# PCB_CHECK_MAIN233-201219.net
KiCad netlist of a schematic drawn in Altium Designer
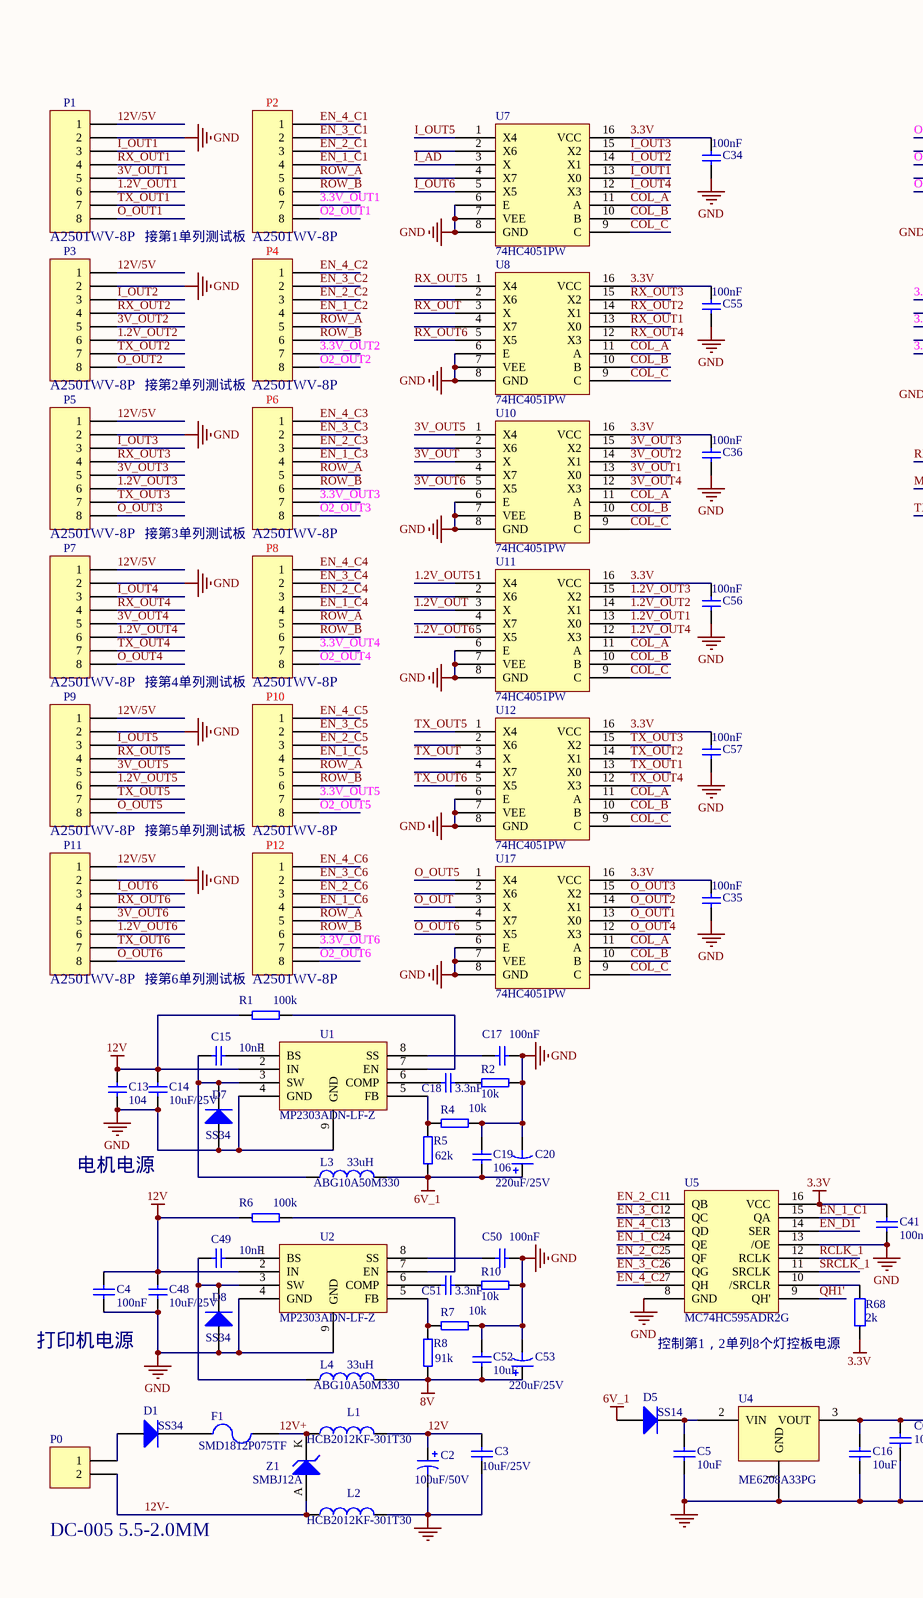
[diagram p0: PCB_CHECK_MAIN233-201219.SchDoc, left]
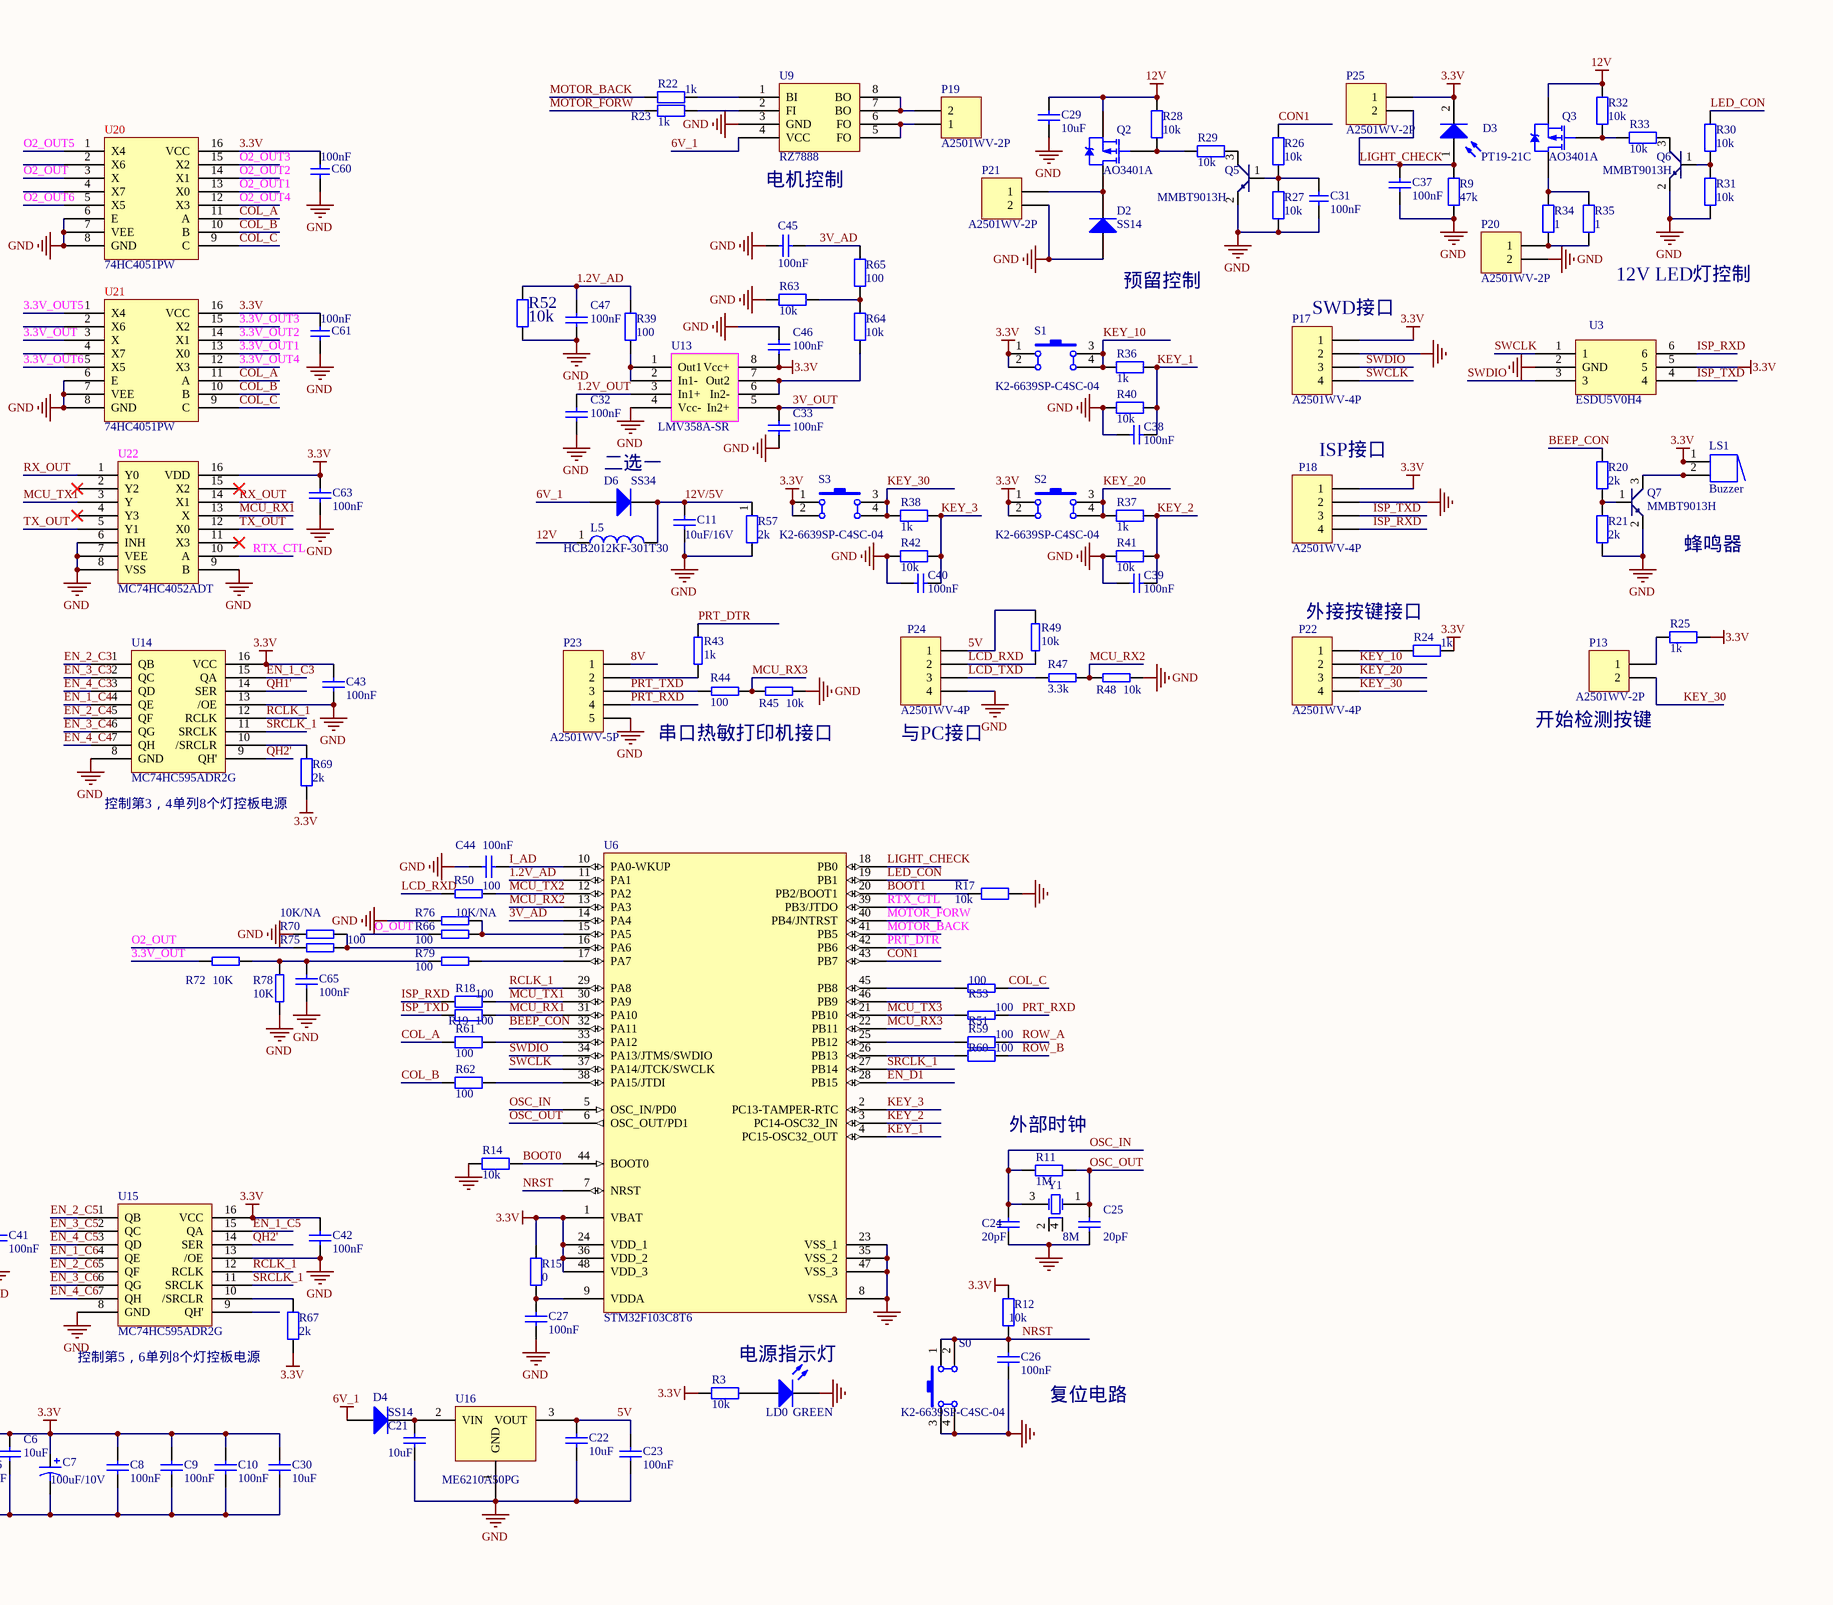
[diagram p1: PCB_CHECK_MAIN233-201219.SchDoc, right]

(export (version "E")
  (design (tool "Eeschema 10.0.6"))
  (components
    (comp (ref "C2")
      (value "100uF/50V")
      (footprint "RB-6*9")
      (description "Polarized Capacitor (Radial)")
      (fields (field (name "PUBLISHER") "Altium Limited"))
      (libsource (lib "Miscellaneous Devices") (part "Cap Pol1"))
    )
    (comp (ref "C3")
      (value "10uF/25V")
      (footprint "C0805")
      (description "Capacitor")
      (fields (field (name "PUBLISHER") "Altium Limited"))
      (libsource (lib "Miscellaneous Devices") (part "Cap"))
    )
    (comp (ref "C4")
      (value "100nF")
      (footprint "C0603")
      (description "Capacitor")
      (fields (field (name "PUBLISHER") "Altium Limited"))
      (libsource (lib "Miscellaneous Devices") (part "Cap"))
    )
    (comp (ref "C5")
      (value "10uF")
      (footprint "C0603")
      (description "Capacitor")
      (fields (field (name "PUBLISHER") "Altium Limited"))
      (libsource (lib "Miscellaneous Devices") (part "Cap"))
    )
    (comp (ref "C6")
      (value "10uF")
      (footprint "C0603")
      (description "Capacitor")
      (fields (field (name "PUBLISHER") "Altium Limited"))
      (libsource (lib "Miscellaneous Devices") (part "Cap"))
    )
    (comp (ref "C7")
      (value "100uF/10V")
      (footprint "C3528")
      (description "Polarized Capacitor (Radial)")
      (fields (field (name "PUBLISHER") "Altium Limited"))
      (libsource (lib "Miscellaneous Devices") (part "Cap Pol1"))
    )
    (comp (ref "C8")
      (value "100nF")
      (footprint "C0603")
      (description "Capacitor")
      (fields (field (name "PUBLISHER") "Altium Limited"))
      (libsource (lib "Miscellaneous Devices") (part "Cap"))
    )
    (comp (ref "C9")
      (value "100nF")
      (footprint "C0603")
      (description "Capacitor")
      (fields (field (name "PUBLISHER") "Altium Limited"))
      (libsource (lib "Miscellaneous Devices") (part "Cap"))
    )
    (comp (ref "C10")
      (value "100nF")
      (footprint "C0603")
      (description "Capacitor")
      (fields (field (name "PUBLISHER") "Altium Limited"))
      (libsource (lib "Miscellaneous Devices") (part "Cap"))
    )
    (comp (ref "C11")
      (value "10uF/16V")
      (footprint "C0603")
      (description "Capacitor")
      (fields (field (name "PUBLISHER") "Altium Limited"))
      (libsource (lib "Miscellaneous Devices") (part "Cap"))
    )
    (comp (ref "C13")
      (value "104")
      (footprint "C0603")
      (description "电容器")
      (libsource (lib "*") (part "Capacitor"))
    )
    (comp (ref "C14")
      (value "10uF/25V")
      (footprint "My Footprint View:C0805")
      (description "电容器")
      (libsource (lib "*") (part "Capacitor"))
    )
    (comp (ref "C15")
      (value "10nF")
      (footprint "C0603")
      (description "电容器")
      (libsource (lib "*") (part "Capacitor"))
    )
    (comp (ref "C16")
      (value "10uF")
      (footprint "C0603")
      (description "Capacitor")
      (fields (field (name "PUBLISHER") "Altium Limited"))
      (libsource (lib "Miscellaneous Devices") (part "Cap"))
    )
    (comp (ref "C17")
      (value "100nF")
      (footprint "C0603")
      (description "电容器")
      (libsource (lib "*") (part "Capacitor"))
    )
    (comp (ref "C18")
      (value "3.3nF")
      (footprint "C0603")
      (description "电容器")
      (libsource (lib "*") (part "Capacitor"))
    )
    (comp (ref "C19")
      (value "106")
      (footprint "C0603")
      (description "电容器")
      (libsource (lib "*") (part "Capacitor"))
    )
    (comp (ref "C20")
      (value "220uF/25V")
      (footprint "RB-6*9")
      (description "Polarized Capacitor (Radial)")
      (fields (field (name "PUBLISHER") "Altium Limited"))
      (libsource (lib "Miscellaneous Devices") (part "Cap Pol1"))
    )
    (comp (ref "C21")
      (value "10uF")
      (footprint "C0603")
      (description "Capacitor")
      (fields (field (name "PUBLISHER") "Altium Limited"))
      (libsource (lib "Miscellaneous Devices") (part "Cap"))
    )
    (comp (ref "C22")
      (value "10uF")
      (footprint "C0603")
      (description "Capacitor")
      (fields (field (name "PUBLISHER") "Altium Limited"))
      (libsource (lib "Miscellaneous Devices") (part "Cap"))
    )
    (comp (ref "C23")
      (value "100nF")
      (footprint "C0603")
      (description "Capacitor")
      (fields (field (name "PUBLISHER") "Altium Limited"))
      (libsource (lib "Miscellaneous Devices") (part "Cap"))
    )
    (comp (ref "C24")
      (value "20pF")
      (footprint "C0603")
      (description "Capacitor")
      (fields (field (name "PUBLISHER") "Altium Limited"))
      (libsource (lib "Miscellaneous Devices") (part "Cap"))
    )
    (comp (ref "C25")
      (value "20pF")
      (footprint "C0603")
      (description "Capacitor")
      (fields (field (name "PUBLISHER") "Altium Limited"))
      (libsource (lib "Miscellaneous Devices") (part "Cap"))
    )
    (comp (ref "C26")
      (value "100nF")
      (footprint "C0603")
      (description "Capacitor")
      (fields (field (name "PUBLISHER") "Altium Limited"))
      (libsource (lib "Miscellaneous Devices") (part "Cap"))
    )
    (comp (ref "C27")
      (value "100nF")
      (footprint "C0603")
      (description "Capacitor")
      (fields (field (name "PUBLISHER") "Altium Limited"))
      (libsource (lib "Miscellaneous Devices") (part "Cap"))
    )
    (comp (ref "C29")
      (value "10uF")
      (footprint "C0603")
      (description "Capacitor")
      (fields (field (name "PUBLISHER") "Altium Limited"))
      (libsource (lib "Miscellaneous Devices") (part "Cap"))
    )
    (comp (ref "C30")
      (value "10uF")
      (footprint "C0603")
      (description "Capacitor")
      (fields (field (name "PUBLISHER") "Altium Limited"))
      (libsource (lib "Miscellaneous Devices") (part "Cap"))
    )
    (comp (ref "C31")
      (value "100nF")
      (footprint "C0603")
      (description "电容器")
      (libsource (lib "*") (part "Capacitor"))
    )
    (comp (ref "C32")
      (value "100nF")
      (footprint "C0603")
      (description "Capacitor")
      (fields (field (name "PUBLISHER") "Altium Limited"))
      (libsource (lib "Miscellaneous Devices") (part "Cap"))
    )
    (comp (ref "C33")
      (value "100nF")
      (footprint "C0603")
      (description "Capacitor")
      (fields (field (name "PUBLISHER") "Altium Limited"))
      (libsource (lib "Miscellaneous Devices") (part "Cap"))
    )
    (comp (ref "C34")
      (value "100nF")
      (footprint "C0603")
      (description "电容器")
      (libsource (lib "*") (part "Capacitor"))
    )
    (comp (ref "C35")
      (value "100nF")
      (footprint "C0603")
      (description "电容器")
      (libsource (lib "*") (part "Capacitor"))
    )
    (comp (ref "C36")
      (value "100nF")
      (footprint "C0603")
      (description "电容器")
      (libsource (lib "*") (part "Capacitor"))
    )
    (comp (ref "C37")
      (value "100nF")
      (footprint "C0603")
      (description "Capacitor")
      (fields (field (name "PUBLISHER") "Altium Limited"))
      (libsource (lib "Miscellaneous Devices") (part "Cap"))
    )
    (comp (ref "C38")
      (value "100nF")
      (footprint "C0603")
      (description "电容器")
      (libsource (lib "*") (part "Capacitor"))
    )
    (comp (ref "C39")
      (value "100nF")
      (footprint "C0603")
      (description "电容器")
      (libsource (lib "*") (part "Capacitor"))
    )
    (comp (ref "C40")
      (value "100nF")
      (footprint "C0603")
      (description "电容器")
      (libsource (lib "*") (part "Capacitor"))
    )
    (comp (ref "C41")
      (value "100nF")
      (footprint "C0603")
      (description "Capacitor")
      (fields (field (name "PUBLISHER") "Altium Limited"))
      (libsource (lib "Miscellaneous Devices") (part "Cap"))
    )
    (comp (ref "C42")
      (value "100nF")
      (footprint "C0603")
      (description "Capacitor")
      (fields (field (name "PUBLISHER") "Altium Limited"))
      (libsource (lib "Miscellaneous Devices") (part "Cap"))
    )
    (comp (ref "C43")
      (value "100nF")
      (footprint "C0603")
      (description "Capacitor")
      (fields (field (name "PUBLISHER") "Altium Limited"))
      (libsource (lib "Miscellaneous Devices") (part "Cap"))
    )
    (comp (ref "C44")
      (value "100nF")
      (footprint "C0603")
      (description "Capacitor")
      (fields (field (name "PUBLISHER") "Altium Limited"))
      (libsource (lib "Miscellaneous Devices") (part "Cap"))
    )
    (comp (ref "C45")
      (value "100nF")
      (footprint "C0603")
      (description "Capacitor")
      (fields (field (name "PUBLISHER") "Altium Limited"))
      (libsource (lib "Miscellaneous Devices") (part "Cap"))
    )
    (comp (ref "C46")
      (value "100nF")
      (footprint "C0603")
      (description "Capacitor")
      (fields (field (name "PUBLISHER") "Altium Limited"))
      (libsource (lib "Miscellaneous Devices") (part "Cap"))
    )
    (comp (ref "C47")
      (value "100nF")
      (footprint "C0603")
      (description "Capacitor")
      (fields (field (name "PUBLISHER") "Altium Limited"))
      (libsource (lib "Miscellaneous Devices") (part "Cap"))
    )
    (comp (ref "C48")
      (value "10uF/25V")
      (footprint "My Footprint View:C0805")
      (description "电容器")
      (libsource (lib "*") (part "Capacitor"))
    )
    (comp (ref "C49")
      (value "10nF")
      (footprint "C0603")
      (description "电容器")
      (libsource (lib "*") (part "Capacitor"))
    )
    (comp (ref "C50")
      (value "100nF")
      (footprint "C0603")
      (description "电容器")
      (libsource (lib "*") (part "Capacitor"))
    )
    (comp (ref "C51")
      (value "3.3nF")
      (footprint "C0603")
      (description "电容器")
      (libsource (lib "*") (part "Capacitor"))
    )
    (comp (ref "C52")
      (value "10uF")
      (footprint "C0603")
      (description "电容器")
      (libsource (lib "*") (part "Capacitor"))
    )
    (comp (ref "C53")
      (value "220uF/25V")
      (footprint "RB-6*9")
      (description "Polarized Capacitor (Radial)")
      (fields (field (name "PUBLISHER") "Altium Limited"))
      (libsource (lib "Miscellaneous Devices") (part "Cap Pol1"))
    )
    (comp (ref "C55")
      (value "100nF")
      (footprint "C0603")
      (description "电容器")
      (libsource (lib "*") (part "Capacitor"))
    )
    (comp (ref "C56")
      (value "100nF")
      (footprint "C0603")
      (description "电容器")
      (libsource (lib "*") (part "Capacitor"))
    )
    (comp (ref "C57")
      (value "100nF")
      (footprint "C0603")
      (description "电容器")
      (libsource (lib "*") (part "Capacitor"))
    )
    (comp (ref "C60")
      (value "100nF")
      (footprint "C0603")
      (description "电容器")
      (libsource (lib "*") (part "Capacitor"))
    )
    (comp (ref "C61")
      (value "100nF")
      (footprint "C0603")
      (description "电容器")
      (libsource (lib "*") (part "Capacitor"))
    )
    (comp (ref "C63")
      (value "100nF")
      (footprint "C0603")
      (description "Capacitor")
      (fields (field (name "PUBLISHER") "Altium Limited"))
      (libsource (lib "Miscellaneous Devices") (part "Cap"))
    )
    (comp (ref "C65")
      (value "100nF")
      (footprint "C0603")
      (description "Capacitor")
      (fields (field (name "PUBLISHER") "Altium Limited"))
      (libsource (lib "Miscellaneous Devices") (part "Cap"))
    )
    (comp (ref "D1")
      (value "SS34")
      (footprint "SMB")
      (description "1 Amp General Purpose Rectifier")
      (fields (field (name "PUBLISHER") "Altium Limited"))
      (libsource (lib "Miscellaneous Devices") (part "Diode 1N4001"))
    )
    (comp (ref "D2")
      (value "SS14")
      (footprint "SOD-123F")
      (description "通用二极管")
      (fields (field (name "PUBLISHER") "Altium Limited"))
      (libsource (lib "*") (part "Diode"))
    )
    (comp (ref "D3")
      (value "PT19-21C")
      (footprint "LED-0603")
      (description "Photosensitive Diode")
      (fields (field (name "PUBLISHER") "Altium Limited"))
      (libsource (lib "Miscellaneous Devices") (part "Photo Sen"))
    )
    (comp (ref "D4")
      (value "SS14")
      (footprint "SOD-123F")
      (description "1 Amp General Purpose Rectifier")
      (fields (field (name "PUBLISHER") "Altium Limited"))
      (libsource (lib "Miscellaneous Devices") (part "Diode 1N4001"))
    )
    (comp (ref "D5")
      (value "SS14")
      (footprint "SOD-123F")
      (description "1 Amp General Purpose Rectifier")
      (fields (field (name "PUBLISHER") "Altium Limited"))
      (libsource (lib "Miscellaneous Devices") (part "Diode 1N4001"))
    )
    (comp (ref "D6")
      (value "SS34")
      (footprint "SMB")
      (description "1 Amp General Purpose Rectifier")
      (fields (field (name "PUBLISHER") "Altium Limited"))
      (libsource (lib "Miscellaneous Devices") (part "Diode 1N4001"))
    )
    (comp (ref "D7")
      (value "SS34")
      (footprint "PCBLIB:SMB")
      (description "通用二极管")
      (fields (field (name "PUBLISHER") "Altium Limited"))
      (libsource (lib "*") (part "Diode"))
    )
    (comp (ref "D8")
      (value "SS34")
      (footprint "PCBLIB:SMB")
      (description "通用二极管")
      (fields (field (name "PUBLISHER") "Altium Limited"))
      (libsource (lib "*") (part "Diode"))
    )
    (comp (ref "F1")
      (value "SMD1812P075TF")
      (footprint "1812")
      (description "Fuse")
      (fields (field (name "PUBLISHER") "Altium Limited"))
      (libsource (lib "Miscellaneous Devices") (part "Fuse 2"))
    )
    (comp (ref "L1")
      (value "HCB2012KF-301T30")
      (footprint "R0805")
      (description "Inductor")
      (fields (field (name "PUBLISHER") "Altium Limited"))
      (libsource (lib "Miscellaneous Devices") (part "Inductor"))
    )
    (comp (ref "L2")
      (value "HCB2012KF-301T30")
      (footprint "R0805")
      (description "Inductor")
      (fields (field (name "PUBLISHER") "Altium Limited"))
      (libsource (lib "Miscellaneous Devices") (part "Inductor"))
    )
    (comp (ref "L3")
      (value "33uH")
      (footprint "L1040")
      (description "Inductor")
      (fields (field (name "ALTIUM_VALUE") "ABG10A50M330") (field (name "PUBLISHER") "Altium Limited"))
      (libsource (lib "") (part "Inductor_2"))
    )
    (comp (ref "L4")
      (value "33uH")
      (footprint "L1040")
      (description "Inductor")
      (fields (field (name "ALTIUM_VALUE") "ABG10A50M330") (field (name "PUBLISHER") "Altium Limited"))
      (libsource (lib "") (part "Inductor_2"))
    )
    (comp (ref "L5")
      (value "HCB2012KF-301T30")
      (footprint "R0805")
      (description "Inductor")
      (fields (field (name "PUBLISHER") "Altium Limited"))
      (libsource (lib "") (part "Inductor_1"))
    )
    (comp (ref "LD0")
      (value "GREEN")
      (footprint "LED-0603")
      (description "LED灯")
      (fields (field (name "PUBLISHER") "Altium Limited"))
      (libsource (lib "*") (part "LED0"))
    )
    (comp (ref "LS1")
      (value "Buzzer")
      (footprint "BUZZER-small")
      (description "Magnetic Transducer Buzzer")
      (fields (field (name "PUBLISHER") "Altium Limited"))
      (libsource (lib "PCB_Project2") (part "Buzzer"))
    )
    (comp (ref "P0")
      (value "DC-005 5.5-2.0MM")
      (footprint "DC-005A")
      (description "Header, 2-Pin")
      (fields (field (name "PUBLISHER") "Altium Limited"))
      (libsource (lib "Miscellaneous Connectors") (part "Header 2"))
    )
    (comp (ref "P1")
      (value "A2501WV-8P")
      (footprint "XH2.5-8P")
      (description "Header, 8-Pin")
      (fields (field (name "PUBLISHER") "Altium Limited"))
      (libsource (lib "Miscellaneous Connectors") (part "Header 8"))
    )
    (comp (ref "P2")
      (value "A2501WV-8P")
      (footprint "XH2.5-8P")
      (description "Header, 8-Pin")
      (fields (field (name "PUBLISHER") "Altium Limited"))
      (libsource (lib "Miscellaneous Connectors") (part "Header 8"))
    )
    (comp (ref "P3")
      (value "A2501WV-8P")
      (footprint "XH2.5-8P")
      (description "Header, 8-Pin")
      (fields (field (name "PUBLISHER") "Altium Limited"))
      (libsource (lib "Miscellaneous Connectors") (part "Header 8"))
    )
    (comp (ref "P4")
      (value "A2501WV-8P")
      (footprint "XH2.5-8P")
      (description "Header, 8-Pin")
      (fields (field (name "PUBLISHER") "Altium Limited"))
      (libsource (lib "Miscellaneous Connectors") (part "Header 8"))
    )
    (comp (ref "P5")
      (value "A2501WV-8P")
      (footprint "XH2.5-8P")
      (description "Header, 8-Pin")
      (fields (field (name "PUBLISHER") "Altium Limited"))
      (libsource (lib "Miscellaneous Connectors") (part "Header 8"))
    )
    (comp (ref "P6")
      (value "A2501WV-8P")
      (footprint "XH2.5-8P")
      (description "Header, 8-Pin")
      (fields (field (name "PUBLISHER") "Altium Limited"))
      (libsource (lib "Miscellaneous Connectors") (part "Header 8"))
    )
    (comp (ref "P7")
      (value "A2501WV-8P")
      (footprint "XH2.5-8P")
      (description "Header, 8-Pin")
      (fields (field (name "PUBLISHER") "Altium Limited"))
      (libsource (lib "Miscellaneous Connectors") (part "Header 8"))
    )
    (comp (ref "P8")
      (value "A2501WV-8P")
      (footprint "XH2.5-8P")
      (description "Header, 8-Pin")
      (fields (field (name "PUBLISHER") "Altium Limited"))
      (libsource (lib "Miscellaneous Connectors") (part "Header 8"))
    )
    (comp (ref "P9")
      (value "A2501WV-8P")
      (footprint "XH2.5-8P")
      (description "Header, 8-Pin")
      (fields (field (name "PUBLISHER") "Altium Limited"))
      (libsource (lib "Miscellaneous Connectors") (part "Header 8"))
    )
    (comp (ref "P10")
      (value "A2501WV-8P")
      (footprint "XH2.5-8P")
      (description "Header, 8-Pin")
      (fields (field (name "PUBLISHER") "Altium Limited"))
      (libsource (lib "Miscellaneous Connectors") (part "Header 8"))
    )
    (comp (ref "P11")
      (value "A2501WV-8P")
      (footprint "XH2.5-8P")
      (description "Header, 8-Pin")
      (fields (field (name "PUBLISHER") "Altium Limited"))
      (libsource (lib "Miscellaneous Connectors") (part "Header 8"))
    )
    (comp (ref "P12")
      (value "A2501WV-8P")
      (footprint "XH2.5-8P")
      (description "Header, 8-Pin")
      (fields (field (name "PUBLISHER") "Altium Limited"))
      (libsource (lib "Miscellaneous Connectors") (part "Header 8"))
    )
    (comp (ref "P13")
      (value "A2501WV-2P")
      (footprint "XH2.5-2P")
      (description "Header, 2-Pin")
      (fields (field (name "PUBLISHER") "Altium Limited"))
      (libsource (lib "*") (part "Header 2"))
    )
    (comp (ref "P17")
      (value "A2501WV-4P")
      (footprint "XH2.5-4P")
      (description "Header, 4-Pin")
      (fields (field (name "PUBLISHER") "Altium Limited"))
      (libsource (lib "*") (part "Header 4"))
    )
    (comp (ref "P18")
      (value "A2501WV-4P")
      (footprint "XH2.5-4P")
      (description "Header, 4-Pin")
      (fields (field (name "PUBLISHER") "Altium Limited"))
      (libsource (lib "*") (part "Header 4"))
    )
    (comp (ref "P19")
      (value "A2501WV-2P")
      (footprint "XH2.5-2P")
      (description "Header, 2-Pin")
      (fields (field (name "PUBLISHER") "Altium Limited"))
      (libsource (lib "") (part "Header 2_1"))
    )
    (comp (ref "P20")
      (value "A2501WV-2P")
      (footprint "XH2.5-2P")
      (description "Header, 2-Pin")
      (fields (field (name "PUBLISHER") "Altium Limited"))
      (libsource (lib "*") (part "Header 2"))
    )
    (comp (ref "P21")
      (value "A2501WV-2P")
      (footprint "XH2.5-2P")
      (description "Header, 2-Pin")
      (fields (field (name "PUBLISHER") "Altium Limited"))
      (libsource (lib "*") (part "Header 2"))
    )
    (comp (ref "P22")
      (value "A2501WV-4P")
      (footprint "XH2.5-4P")
      (description "Header, 4-Pin")
      (fields (field (name "PUBLISHER") "Altium Limited"))
      (libsource (lib "*") (part "Header 4"))
    )
    (comp (ref "P23")
      (value "A2501WV-5P")
      (footprint "PcbLib1:XH2.5-5P")
      (description "Header, 5-Pin")
      (fields (field (name "PUBLISHER") "Altium Limited"))
      (libsource (lib "Miscellaneous Connectors") (part "Header 5"))
    )
    (comp (ref "P24")
      (value "A2501WV-4P")
      (footprint "XH2.5-4P")
      (description "Header, 4-Pin")
      (fields (field (name "PUBLISHER") "Altium Limited"))
      (libsource (lib "*") (part "Header 4"))
    )
    (comp (ref "P25")
      (value "A2501WV-2P")
      (footprint "XH2.5-2P")
      (description "Header, 2-Pin")
      (fields (field (name "PUBLISHER") "Altium Limited"))
      (libsource (lib "*") (part "Header 2"))
    )
    (comp (ref "Q2")
      (value "AO3401A")
      (footprint "SOT-23")
      (description "P-Channel MOSFET")
      (fields (field (name "PUBLISHER") "Altium Limited"))
      (libsource (lib "MY_STD_SCH") (part "MY_MOSFET-P"))
    )
    (comp (ref "Q3")
      (value "AO3401A")
      (footprint "SOT-23")
      (description "P-Channel MOSFET")
      (fields (field (name "PUBLISHER") "Altium Limited"))
      (libsource (lib "MY_STD_SCH") (part "MY_MOSFET-P"))
    )
    (comp (ref "Q5")
      (value "MMBT9013H")
      (footprint "SOT-23")
      (description "8050/BCW846/BCW847")
      (libsource (lib "MY_STD_SCH") (part "MY_NPN"))
    )
    (comp (ref "Q6")
      (value "MMBT9013H")
      (footprint "SOT-23")
      (description "8050/BCW846/BCW847")
      (libsource (lib "MY_STD_SCH") (part "MY_NPN"))
    )
    (comp (ref "Q7")
      (value "MMBT9013H")
      (footprint "SOT-23")
      (description "8050/BCW846/BCW847")
      (libsource (lib "MY_STD_SCH") (part "MY_NPN"))
    )
    (comp (ref "R1")
      (value "100k")
      (footprint "R0603")
      (description "电阻器")
      (libsource (lib "*") (part "Resistance"))
    )
    (comp (ref "R2")
      (value "10k")
      (footprint "R0603")
      (description "电阻器")
      (libsource (lib "*") (part "Resistance"))
    )
    (comp (ref "R3")
      (value "10k")
      (footprint "R0603")
      (description "Resistor")
      (fields (field (name "PUBLISHER") "Altium Limited"))
      (libsource (lib "") (part "Res2_1"))
    )
    (comp (ref "R4")
      (value "10k")
      (footprint "R0603")
      (description "电阻器")
      (libsource (lib "*") (part "Resistance"))
    )
    (comp (ref "R5")
      (value "62k")
      (footprint "R0603")
      (description "电阻器")
      (libsource (lib "*") (part "Resistance"))
    )
    (comp (ref "R6")
      (value "100k")
      (footprint "R0603")
      (description "电阻器")
      (libsource (lib "*") (part "Resistance"))
    )
    (comp (ref "R7")
      (value "10k")
      (footprint "R0603")
      (description "电阻器")
      (libsource (lib "*") (part "Resistance"))
    )
    (comp (ref "R8")
      (value "91k")
      (footprint "R0603")
      (description "电阻器")
      (libsource (lib "*") (part "Resistance"))
    )
    (comp (ref "R9")
      (value "47k")
      (footprint "R0603")
      (description "Resistor")
      (fields (field (name "PUBLISHER") "Altium Limited"))
      (libsource (lib "") (part "Res2_2"))
    )
    (comp (ref "R10")
      (value "10k")
      (footprint "R0603")
      (description "电阻器")
      (libsource (lib "*") (part "Resistance"))
    )
    (comp (ref "R11")
      (value "1M")
      (footprint "R0603")
      (description "Resistor")
      (fields (field (name "PUBLISHER") "Altium Limited"))
      (libsource (lib "") (part "Res2_1"))
    )
    (comp (ref "R12")
      (value "10k")
      (footprint "R0603")
      (description "Resistor")
      (fields (field (name "PUBLISHER") "Altium Limited"))
      (libsource (lib "") (part "Res2_4"))
    )
    (comp (ref "R14")
      (value "10k")
      (footprint "R0603")
      (description "Resistor")
      (fields (field (name "PUBLISHER") "Altium Limited"))
      (libsource (lib "") (part "Res2_1"))
    )
    (comp (ref "R15")
      (value "0")
      (footprint "R0603")
      (description "Resistor")
      (fields (field (name "PUBLISHER") "Altium Limited"))
      (libsource (lib "") (part "Res2_4"))
    )
    (comp (ref "R17")
      (value "10k")
      (footprint "R0603")
      (description "Resistor")
      (fields (field (name "PUBLISHER") "Altium Limited"))
      (libsource (lib "Miscellaneous Devices") (part "Res2"))
    )
    (comp (ref "R18")
      (value "100")
      (footprint "R0603")
      (description "Resistor")
      (fields (field (name "PUBLISHER") "Altium Limited"))
      (libsource (lib "") (part "Res2_1"))
    )
    (comp (ref "R19")
      (value "100")
      (footprint "R0603")
      (description "Resistor")
      (fields (field (name "PUBLISHER") "Altium Limited"))
      (libsource (lib "") (part "Res2_1"))
    )
    (comp (ref "R20")
      (value "2k")
      (footprint "R0603")
      (description "Resistor")
      (fields (field (name "PUBLISHER") "Altium Limited"))
      (libsource (lib "") (part "Res2_2"))
    )
    (comp (ref "R21")
      (value "2k")
      (footprint "R0603")
      (description "Resistor")
      (fields (field (name "PUBLISHER") "Altium Limited"))
      (libsource (lib "") (part "Res2_4"))
    )
    (comp (ref "R22")
      (value "1k")
      (footprint "R0603")
      (description "Resistor")
      (fields (field (name "PUBLISHER") "Altium Limited"))
      (libsource (lib "") (part "Res2_4"))
    )
    (comp (ref "R23")
      (value "1k")
      (footprint "R0603")
      (description "Resistor")
      (fields (field (name "PUBLISHER") "Altium Limited"))
      (libsource (lib "") (part "Res2_2"))
    )
    (comp (ref "R24")
      (value "1k")
      (footprint "R0603")
      (description "Resistor")
      (fields (field (name "PUBLISHER") "Altium Limited"))
      (libsource (lib "Miscellaneous Devices") (part "Res2"))
    )
    (comp (ref "R25")
      (value "1k")
      (footprint "R0603")
      (description "Resistor")
      (fields (field (name "PUBLISHER") "Altium Limited"))
      (libsource (lib "Miscellaneous Devices") (part "Res2"))
    )
    (comp (ref "R26")
      (value "10k")
      (footprint "R0603")
      (description "Resistor")
      (fields (field (name "PUBLISHER") "Altium Limited"))
      (libsource (lib "Miscellaneous Devices") (part "Res2"))
    )
    (comp (ref "R27")
      (value "10k")
      (footprint "R0603")
      (description "Resistor")
      (fields (field (name "PUBLISHER") "Altium Limited"))
      (libsource (lib "") (part "Res2_1"))
    )
    (comp (ref "R28")
      (value "10k")
      (footprint "R0603")
      (description "Resistor")
      (fields (field (name "PUBLISHER") "Altium Limited"))
      (libsource (lib "") (part "Res2_1"))
    )
    (comp (ref "R29")
      (value "10k")
      (footprint "R0603")
      (description "Resistor")
      (fields (field (name "PUBLISHER") "Altium Limited"))
      (libsource (lib "") (part "Res2_2"))
    )
    (comp (ref "R30")
      (value "10k")
      (footprint "R0603")
      (description "Resistor")
      (fields (field (name "PUBLISHER") "Altium Limited"))
      (libsource (lib "Miscellaneous Devices") (part "Res2"))
    )
    (comp (ref "R31")
      (value "10k")
      (footprint "R0603")
      (description "Resistor")
      (fields (field (name "PUBLISHER") "Altium Limited"))
      (libsource (lib "") (part "Res2_1"))
    )
    (comp (ref "R32")
      (value "10k")
      (footprint "R0603")
      (description "Resistor")
      (fields (field (name "PUBLISHER") "Altium Limited"))
      (libsource (lib "") (part "Res2_1"))
    )
    (comp (ref "R33")
      (value "10k")
      (footprint "R0603")
      (description "Resistor")
      (fields (field (name "PUBLISHER") "Altium Limited"))
      (libsource (lib "") (part "Res2_2"))
    )
    (comp (ref "R34")
      (value "1")
      (footprint "R1206")
      (description "Resistor")
      (fields (field (name "PUBLISHER") "Altium Limited"))
      (libsource (lib "") (part "Res2_1"))
    )
    (comp (ref "R35")
      (value "1")
      (footprint "R1206")
      (description "Resistor")
      (fields (field (name "PUBLISHER") "Altium Limited"))
      (libsource (lib "") (part "Res2_1"))
    )
    (comp (ref "R36")
      (value "1k")
      (footprint "R0603")
      (description "Resistor")
      (fields (field (name "PUBLISHER") "Altium Limited"))
      (libsource (lib "Miscellaneous Devices") (part "Res2"))
    )
    (comp (ref "R37")
      (value "1k")
      (footprint "R0603")
      (description "Resistor")
      (fields (field (name "PUBLISHER") "Altium Limited"))
      (libsource (lib "Miscellaneous Devices") (part "Res2"))
    )
    (comp (ref "R38")
      (value "1k")
      (footprint "R0603")
      (description "Resistor")
      (fields (field (name "PUBLISHER") "Altium Limited"))
      (libsource (lib "Miscellaneous Devices") (part "Res2"))
    )
    (comp (ref "R39")
      (value "100")
      (footprint "R0603")
      (description "Resistor")
      (fields (field (name "PUBLISHER") "Altium Limited"))
      (libsource (lib "") (part "Res2_2"))
    )
    (comp (ref "R40")
      (value "10k")
      (footprint "R0603")
      (description "Resistor")
      (fields (field (name "PUBLISHER") "Altium Limited"))
      (libsource (lib "Miscellaneous Devices") (part "Res2"))
    )
    (comp (ref "R41")
      (value "10k")
      (footprint "R0603")
      (description "Resistor")
      (fields (field (name "PUBLISHER") "Altium Limited"))
      (libsource (lib "Miscellaneous Devices") (part "Res2"))
    )
    (comp (ref "R42")
      (value "10k")
      (footprint "R0603")
      (description "Resistor")
      (fields (field (name "PUBLISHER") "Altium Limited"))
      (libsource (lib "Miscellaneous Devices") (part "Res2"))
    )
    (comp (ref "R43")
      (value "1k")
      (footprint "R0603")
      (description "电阻器")
      (libsource (lib "*") (part "Resistance"))
    )
    (comp (ref "R44")
      (value "100")
      (footprint "R0603")
      (description "电阻器")
      (libsource (lib "*") (part "Resistance"))
    )
    (comp (ref "R45")
      (value "10k")
      (footprint "R0603")
      (description "电阻器")
      (libsource (lib "*") (part "Resistance"))
    )
    (comp (ref "R47")
      (value "3.3k")
      (footprint "R0603")
      (description "电阻器")
      (libsource (lib "*") (part "Resistance"))
    )
    (comp (ref "R48")
      (value "10k")
      (footprint "R0603")
      (description "电阻器")
      (libsource (lib "*") (part "Resistance"))
    )
    (comp (ref "R49")
      (value "10k")
      (footprint "R0603")
      (description "电阻器")
      (libsource (lib "*") (part "Resistance"))
    )
    (comp (ref "R50")
      (value "100")
      (footprint "R0603")
      (description "电阻器")
      (libsource (lib "*") (part "Resistance"))
    )
    (comp (ref "R51")
      (value "100")
      (footprint "R0603")
      (description "电阻器")
      (libsource (lib "*") (part "Resistance"))
    )
    (comp (ref "R52")
      (value "10k")
      (footprint "R0603")
      (description "Resistor")
      (fields (field (name "PUBLISHER") "Altium Limited"))
      (libsource (lib "") (part "Res2_2"))
    )
    (comp (ref "R53")
      (value "100")
      (footprint "R0603")
      (description "电阻器")
      (libsource (lib "*") (part "Resistance"))
    )
    (comp (ref "R57")
      (value "2k")
      (footprint "R0603")
      (description "Resistor")
      (fields (field (name "PUBLISHER") "Altium Limited"))
      (libsource (lib "") (part "Res2_3"))
    )
    (comp (ref "R59")
      (value "100")
      (footprint "R0603")
      (description "Resistor")
      (fields (field (name "PUBLISHER") "Altium Limited"))
      (libsource (lib "Miscellaneous Devices") (part "Res2"))
    )
    (comp (ref "R60")
      (value "100")
      (footprint "R0603")
      (description "Resistor")
      (fields (field (name "PUBLISHER") "Altium Limited"))
      (libsource (lib "Miscellaneous Devices") (part "Res2"))
    )
    (comp (ref "R61")
      (value "100")
      (footprint "R0603")
      (description "Resistor")
      (fields (field (name "PUBLISHER") "Altium Limited"))
      (libsource (lib "") (part "Res2_1"))
    )
    (comp (ref "R62")
      (value "100")
      (footprint "R0603")
      (description "Resistor")
      (fields (field (name "PUBLISHER") "Altium Limited"))
      (libsource (lib "") (part "Res2_1"))
    )
    (comp (ref "R63")
      (value "10k")
      (footprint "R0603")
      (description "Resistor")
      (fields (field (name "PUBLISHER") "Altium Limited"))
      (libsource (lib "Miscellaneous Devices") (part "Res2"))
    )
    (comp (ref "R64")
      (value "10k")
      (footprint "R0603")
      (description "Resistor")
      (fields (field (name "PUBLISHER") "Altium Limited"))
      (libsource (lib "") (part "Res2_4"))
    )
    (comp (ref "R65")
      (value "100")
      (footprint "R0603")
      (description "Resistor")
      (fields (field (name "PUBLISHER") "Altium Limited"))
      (libsource (lib "") (part "Res2_2"))
    )
    (comp (ref "R66")
      (value "100")
      (footprint "R0603")
      (description "电阻器")
      (libsource (lib "*") (part "Resistance"))
    )
    (comp (ref "R67")
      (value "2k")
      (footprint "R0603")
      (description "Resistor")
      (fields (field (name "PUBLISHER") "Altium Limited"))
      (libsource (lib "") (part "Res2_4"))
    )
    (comp (ref "R68")
      (value "2k")
      (footprint "R0603")
      (description "Resistor")
      (fields (field (name "PUBLISHER") "Altium Limited"))
      (libsource (lib "") (part "Res2_4"))
    )
    (comp (ref "R69")
      (value "2k")
      (footprint "R0603")
      (description "Resistor")
      (fields (field (name "PUBLISHER") "Altium Limited"))
      (libsource (lib "") (part "Res2_4"))
    )
    (comp (ref "R70")
      (value "10K/NA")
      (footprint "R0603")
      (description "电阻器")
      (libsource (lib "*") (part "Resistance"))
    )
    (comp (ref "R72")
      (value "10K")
      (footprint "R0603")
      (description "电阻器")
      (libsource (lib "*") (part "Resistance"))
    )
    (comp (ref "R75")
      (value "100")
      (footprint "R0603")
      (description "电阻器")
      (libsource (lib "*") (part "Resistance"))
    )
    (comp (ref "R76")
      (value "10K/NA")
      (footprint "R0603")
      (description "电阻器")
      (libsource (lib "*") (part "Resistance"))
    )
    (comp (ref "R78")
      (value "10K")
      (footprint "R0603")
      (description "电阻器")
      (libsource (lib "*") (part "Resistance"))
    )
    (comp (ref "R79")
      (value "100")
      (footprint "R0603")
      (description "电阻器")
      (libsource (lib "*") (part "Resistance"))
    )
    (comp (ref "S0")
      (value "K2-6639SP-C4SC-04")
      (footprint "MY_KEYSOP4")
      (description "Switch")
      (fields (field (name "PUBLISHER") "Altium Limited"))
      (libsource (lib "MYSCH") (part "SW-PB-4pin"))
    )
    (comp (ref "S1")
      (value "K2-6639SP-C4SC-04")
      (footprint "MY_KEYSOP4")
      (description "Switch")
      (fields (field (name "PUBLISHER") "Altium Limited"))
      (libsource (lib "MYSCH") (part "SW-PB-4pin"))
    )
    (comp (ref "S2")
      (value "K2-6639SP-C4SC-04")
      (footprint "MY_KEYSOP4")
      (description "Switch")
      (fields (field (name "PUBLISHER") "Altium Limited"))
      (libsource (lib "MYSCH") (part "SW-PB-4pin"))
    )
    (comp (ref "S3")
      (value "K2-6639SP-C4SC-04")
      (footprint "MY_KEYSOP4")
      (description "Switch")
      (fields (field (name "PUBLISHER") "Altium Limited"))
      (libsource (lib "MYSCH") (part "SW-PB-4pin"))
    )
    (comp (ref "U1")
      (value "MP2303ADN-LF-Z")
      (footprint "SO-8-EP")
      (libsource (lib "Schlib1") (part "TD1519A"))
    )
    (comp (ref "U2")
      (value "MP2303ADN-LF-Z")
      (footprint "SO-8-EP")
      (libsource (lib "Schlib1") (part "TD1519A"))
    )
    (comp (ref "U3")
      (value "ESDU5V0H4")
      (footprint "SOT-23-6")
      (libsource (lib "Schlib11") (part "CESDLC5V0M5"))
    )
    (comp (ref "U4")
      (value "ME6208A33PG")
      (footprint "My Footprint View:SOT89N")
      (libsource (lib "Schlib1") (part "ME6208A50PG"))
    )
    (comp (ref "U5")
      (value "MC74HC595ADR2G")
      (footprint "PCBLIB:SOP16_M")
      (libsource (lib "Schlib1") (part "74HC595"))
    )
    (comp (ref "U6")
      (value "STM32F103C8T6")
      (footprint "LQFP-48-1")
      (description "STM32 ARM-based 32-bit MCU with 64 Kbytes Flash, 48-pin LQFP, Industrial Temperature")
      (fields (field (name "PUBLISHER") "Altium Limited"))
      (libsource (lib "ST Microcontroller 32-Bit STM32") (part "STM32F103C8T6"))
    )
    (comp (ref "U7") (value "74HC4051PW") (footprint "TSSOP16_N") (libsource (lib "Schlib1") (part "CD4051")))
    (comp (ref "U8") (value "74HC4051PW") (footprint "TSSOP16_N") (libsource (lib "Schlib1") (part "CD4051")))
    (comp (ref "U9")
      (value "RZ7888")
      (footprint "My Footprint View:SO-8S")
      (libsource (lib "Schlib1") (part "RZ7888"))
    )
    (comp (ref "U10")
      (value "74HC4051PW")
      (footprint "TSSOP16_N")
      (libsource (lib "Schlib1") (part "CD4051"))
    )
    (comp (ref "U11")
      (value "74HC4051PW")
      (footprint "TSSOP16_N")
      (libsource (lib "Schlib1") (part "CD4051"))
    )
    (comp (ref "U12")
      (value "74HC4051PW")
      (footprint "TSSOP16_N")
      (libsource (lib "Schlib1") (part "CD4051"))
    )
    (comp (ref "U13")
      (value "LMV358A-SR")
      (footprint "SO-8S")
      (description "dual-op")
      (libsource (lib "X-band-chip") (part "LM358"))
    )
    (comp (ref "U14")
      (value "MC74HC595ADR2G")
      (footprint "PCBLIB:SOP16_M")
      (libsource (lib "Schlib1") (part "74HC595"))
    )
    (comp (ref "U15")
      (value "MC74HC595ADR2G")
      (footprint "PCBLIB:SOP16_M")
      (libsource (lib "Schlib1") (part "74HC595"))
    )
    (comp (ref "U16")
      (value "ME6210A50PG")
      (footprint "My Footprint View:SOT89N")
      (libsource (lib "Schlib1") (part "ME6208A50PG"))
    )
    (comp (ref "U17")
      (value "74HC4051PW")
      (footprint "TSSOP16_N")
      (libsource (lib "Schlib1") (part "CD4051"))
    )
    (comp (ref "U20")
      (value "74HC4051PW")
      (footprint "TSSOP16_N")
      (libsource (lib "Schlib1") (part "CD4051"))
    )
    (comp (ref "U21")
      (value "74HC4051PW")
      (footprint "TSSOP16_N")
      (libsource (lib "Schlib1") (part "CD4051"))
    )
    (comp (ref "U22")
      (value "MC74HC4052ADT")
      (footprint "TSSOP16_N")
      (libsource (lib "Schlib1") (part "CD4052"))
    )
    (comp (ref "Y1")
      (value "8M")
      (footprint "CRYSTAL_3.2*2.5")
      (libsource (lib "schlib-yves20140829") (part "CRYSTAL-PASSIVE_3225"))
    )
    (comp (ref "Z1")
      (value "SMBJ12A")
      (footprint "PCBLIB:SMB")
      (description "Zener Diode")
      (fields (field (name "PUBLISHER") "Altium Limited"))
      (libsource (lib "Miscellaneous Devices") (part "D Zener"))
    )
  )
  (nets
    (net (code "1") (name "/1.2V_AD") (class "Default")
      (node (ref "C47") (pin "2") (pinfunction "2_2") (pintype "passive"))
      (node (ref "R39") (pin "1") (pinfunction "1_1") (pintype "passive"))
      (node (ref "R52") (pin "1") (pinfunction "1_1") (pintype "passive"))
      (node (ref "U6") (pin "11") (pinfunction "PA1_11") (pintype "bidirectional"))
    )
    (net (code "2") (name "/1.2V_OUT") (class "Default")
      (node (ref "C32") (pin "2") (pinfunction "2_2") (pintype "passive"))
      (node (ref "U11") (pin "3") (pinfunction "X_3") (pintype "passive"))
      (node (ref "U13") (pin "3") (pinfunction "In1+_3") (pintype "passive"))
    )
    (net (code "3") (name "/1.2V_OUT1") (class "Default")
      (node (ref "P1") (pin "6") (pinfunction "6_6") (pintype "passive"))
      (node (ref "U11") (pin "13") (pinfunction "X0_13") (pintype "passive"))
    )
    (net (code "4") (name "/1.2V_OUT2") (class "Default")
      (node (ref "P3") (pin "6") (pinfunction "6_6") (pintype "passive"))
      (node (ref "U11") (pin "14") (pinfunction "X1_14") (pintype "passive"))
    )
    (net (code "5") (name "/1.2V_OUT3") (class "Default")
      (node (ref "P5") (pin "6") (pinfunction "6_6") (pintype "passive"))
      (node (ref "U11") (pin "15") (pinfunction "X2_15") (pintype "passive"))
    )
    (net (code "6") (name "/1.2V_OUT4") (class "Default")
      (node (ref "P7") (pin "6") (pinfunction "6_6") (pintype "passive"))
      (node (ref "U11") (pin "12") (pinfunction "X3_12") (pintype "passive"))
    )
    (net (code "7") (name "/1.2V_OUT5") (class "Default")
      (node (ref "P9") (pin "6") (pinfunction "6_6") (pintype "passive"))
      (node (ref "U11") (pin "1") (pinfunction "X4_1") (pintype "passive"))
    )
    (net (code "8") (name "/1.2V_OUT6") (class "Default")
      (node (ref "P11") (pin "6") (pinfunction "6_6") (pintype "passive"))
      (node (ref "U11") (pin "5") (pinfunction "X5_5") (pintype "passive"))
    )
    (net (code "9") (name "/3.3V_OUT") (class "Default")
      (node (ref "R72") (pin "1") (pinfunction "1_1") (pintype "passive"))
      (node (ref "U21") (pin "3") (pinfunction "X_3") (pintype "passive"))
    )
    (net (code "10") (name "/3.3V_OUT1") (class "Default")
      (node (ref "P2") (pin "7") (pinfunction "7_7") (pintype "passive"))
      (node (ref "U21") (pin "13") (pinfunction "X0_13") (pintype "passive"))
    )
    (net (code "11") (name "/3.3V_OUT2") (class "Default")
      (node (ref "P4") (pin "7") (pinfunction "7_7") (pintype "passive"))
      (node (ref "U21") (pin "14") (pinfunction "X1_14") (pintype "passive"))
    )
    (net (code "12") (name "/3.3V_OUT3") (class "Default")
      (node (ref "P6") (pin "7") (pinfunction "7_7") (pintype "passive"))
      (node (ref "U21") (pin "15") (pinfunction "X2_15") (pintype "passive"))
    )
    (net (code "13") (name "/3.3V_OUT4") (class "Default")
      (node (ref "P8") (pin "7") (pinfunction "7_7") (pintype "passive"))
      (node (ref "U21") (pin "12") (pinfunction "X3_12") (pintype "passive"))
    )
    (net (code "14") (name "/3.3V_OUT5") (class "Default")
      (node (ref "P10") (pin "7") (pinfunction "7_7") (pintype "passive"))
      (node (ref "U21") (pin "1") (pinfunction "X4_1") (pintype "passive"))
    )
    (net (code "15") (name "/3.3V_OUT6") (class "Default")
      (node (ref "P12") (pin "7") (pinfunction "7_7") (pintype "passive"))
      (node (ref "U21") (pin "5") (pinfunction "X5_5") (pintype "passive"))
    )
    (net (code "16") (name "/3V_AD") (class "Default")
      (node (ref "C45") (pin "1") (pinfunction "1_1") (pintype "passive"))
      (node (ref "R65") (pin "1") (pinfunction "1_1") (pintype "passive"))
      (node (ref "U6") (pin "14") (pinfunction "PA4_14") (pintype "bidirectional"))
    )
    (net (code "17") (name "/3V_OUT") (class "Default")
      (node (ref "C33") (pin "2") (pinfunction "2_2") (pintype "passive"))
      (node (ref "U10") (pin "3") (pinfunction "X_3") (pintype "passive"))
      (node (ref "U13") (pin "5") (pinfunction "In2+_5") (pintype "passive"))
    )
    (net (code "18") (name "/3V_OUT1") (class "Default")
      (node (ref "P1") (pin "5") (pinfunction "5_5") (pintype "passive"))
      (node (ref "U10") (pin "13") (pinfunction "X0_13") (pintype "passive"))
    )
    (net (code "19") (name "/3V_OUT2") (class "Default")
      (node (ref "P3") (pin "5") (pinfunction "5_5") (pintype "passive"))
      (node (ref "U10") (pin "14") (pinfunction "X1_14") (pintype "passive"))
    )
    (net (code "20") (name "/3V_OUT3") (class "Default")
      (node (ref "P5") (pin "5") (pinfunction "5_5") (pintype "passive"))
      (node (ref "U10") (pin "15") (pinfunction "X2_15") (pintype "passive"))
    )
    (net (code "21") (name "/3V_OUT4") (class "Default")
      (node (ref "P7") (pin "5") (pinfunction "5_5") (pintype "passive"))
      (node (ref "U10") (pin "12") (pinfunction "X3_12") (pintype "passive"))
    )
    (net (code "22") (name "/3V_OUT5") (class "Default")
      (node (ref "P9") (pin "5") (pinfunction "5_5") (pintype "passive"))
      (node (ref "U10") (pin "1") (pinfunction "X4_1") (pintype "passive"))
    )
    (net (code "23") (name "/3V_OUT6") (class "Default")
      (node (ref "P11") (pin "5") (pinfunction "5_5") (pintype "passive"))
      (node (ref "U10") (pin "5") (pinfunction "X5_5") (pintype "passive"))
    )
    (net (code "24") (name "/5V") (class "Default")
      (node (ref "C22") (pin "1") (pinfunction "1_1") (pintype "passive"))
      (node (ref "C23") (pin "2") (pinfunction "2_2") (pintype "passive"))
      (node (ref "P24") (pin "1") (pinfunction "1_1") (pintype "passive"))
      (node (ref "R49") (pin "2") (pinfunction "2_2") (pintype "passive"))
      (node (ref "U16") (pin "3") (pinfunction "VOUT_3") (pintype "passive"))
    )
    (net (code "25") (name "/12V+") (class "Default")
      (node (ref "F1") (pin "2") (pinfunction "2_2") (pintype "passive"))
      (node (ref "L1") (pin "2") (pinfunction "2_2") (pintype "passive"))
      (node (ref "Z1") (pin "K") (pinfunction "K_K") (pintype "passive"))
    )
    (net (code "26") (name "/12V-") (class "Default")
      (node (ref "L2") (pin "2") (pinfunction "2_2") (pintype "passive"))
      (node (ref "P0") (pin "2") (pinfunction "2_2") (pintype "passive"))
      (node (ref "Z1") (pin "A") (pinfunction "A_A") (pintype "passive"))
    )
    (net (code "27") (name "/12V{slash}5V") (class "Default")
      (node (ref "C11") (pin "1") (pinfunction "1_1") (pintype "passive"))
      (node (ref "D6") (pin "2") (pinfunction "K_2") (pintype "passive"))
      (node (ref "L5") (pin "2") (pinfunction "2_2") (pintype "passive"))
      (node (ref "P1") (pin "1") (pinfunction "1_1") (pintype "passive"))
      (node (ref "P11") (pin "1") (pinfunction "1_1") (pintype "passive"))
      (node (ref "P3") (pin "1") (pinfunction "1_1") (pintype "passive"))
      (node (ref "P5") (pin "1") (pinfunction "1_1") (pintype "passive"))
      (node (ref "P7") (pin "1") (pinfunction "1_1") (pintype "passive"))
      (node (ref "P9") (pin "1") (pinfunction "1_1") (pintype "passive"))
      (node (ref "R57") (pin "1") (pinfunction "1_1") (pintype "passive"))
    )
    (net (code "28") (name "/BEEP_CON") (class "Default")
      (node (ref "R20") (pin "1") (pinfunction "1_1") (pintype "passive"))
      (node (ref "U6") (pin "32") (pinfunction "PA11_32") (pintype "bidirectional"))
    )
    (net (code "29") (name "/BOOT0") (class "Default")
      (node (ref "R14") (pin "2") (pinfunction "2_2") (pintype "passive"))
      (node (ref "U6") (pin "44") (pinfunction "BOOT0_44") (pintype "input"))
    )
    (net (code "30") (name "/BOOT1") (class "Default")
      (node (ref "R17") (pin "2") (pinfunction "2_2") (pintype "passive"))
      (node (ref "U6") (pin "20") (pinfunction "PB2/BOOT1_20") (pintype "bidirectional"))
    )
    (net (code "31") (name "/COL_A") (class "Default")
      (node (ref "R61") (pin "1") (pinfunction "1_1") (pintype "passive"))
      (node (ref "U10") (pin "11") (pinfunction "A_11") (pintype "passive"))
      (node (ref "U11") (pin "11") (pinfunction "A_11") (pintype "passive"))
      (node (ref "U12") (pin "11") (pinfunction "A_11") (pintype "passive"))
      (node (ref "U17") (pin "11") (pinfunction "A_11") (pintype "passive"))
      (node (ref "U20") (pin "11") (pinfunction "A_11") (pintype "passive"))
      (node (ref "U21") (pin "11") (pinfunction "A_11") (pintype "passive"))
      (node (ref "U7") (pin "11") (pinfunction "A_11") (pintype "passive"))
      (node (ref "U8") (pin "11") (pinfunction "A_11") (pintype "passive"))
    )
    (net (code "32") (name "/COL_B") (class "Default")
      (node (ref "R62") (pin "1") (pinfunction "1_1") (pintype "passive"))
      (node (ref "U10") (pin "10") (pinfunction "B_10") (pintype "passive"))
      (node (ref "U11") (pin "10") (pinfunction "B_10") (pintype "passive"))
      (node (ref "U12") (pin "10") (pinfunction "B_10") (pintype "passive"))
      (node (ref "U17") (pin "10") (pinfunction "B_10") (pintype "passive"))
      (node (ref "U20") (pin "10") (pinfunction "B_10") (pintype "passive"))
      (node (ref "U21") (pin "10") (pinfunction "B_10") (pintype "passive"))
      (node (ref "U7") (pin "10") (pinfunction "B_10") (pintype "passive"))
      (node (ref "U8") (pin "10") (pinfunction "B_10") (pintype "passive"))
    )
    (net (code "33") (name "/COL_C") (class "Default")
      (node (ref "R53") (pin "1") (pinfunction "1_1") (pintype "passive"))
      (node (ref "U10") (pin "9") (pinfunction "C_9") (pintype "passive"))
      (node (ref "U11") (pin "9") (pinfunction "C_9") (pintype "passive"))
      (node (ref "U12") (pin "9") (pinfunction "C_9") (pintype "passive"))
      (node (ref "U17") (pin "9") (pinfunction "C_9") (pintype "passive"))
      (node (ref "U20") (pin "9") (pinfunction "C_9") (pintype "passive"))
      (node (ref "U21") (pin "9") (pinfunction "C_9") (pintype "passive"))
      (node (ref "U7") (pin "9") (pinfunction "C_9") (pintype "passive"))
      (node (ref "U8") (pin "9") (pinfunction "C_9") (pintype "passive"))
    )
    (net (code "34") (name "/CON1") (class "Default")
      (node (ref "R26") (pin "1") (pinfunction "1_1") (pintype "passive"))
      (node (ref "U6") (pin "43") (pinfunction "PB7_43") (pintype "bidirectional"))
    )
    (net (code "35") (name "/EN_1_C1") (class "Default")
      (node (ref "P2") (pin "4") (pinfunction "4_4") (pintype "passive"))
      (node (ref "U5") (pin "15") (pinfunction "QA_15") (pintype "passive"))
    )
    (net (code "36") (name "/EN_1_C2") (class "Default")
      (node (ref "P4") (pin "4") (pinfunction "4_4") (pintype "passive"))
      (node (ref "U5") (pin "4") (pinfunction "QE_4") (pintype "passive"))
    )
    (net (code "37") (name "/EN_1_C3") (class "Default")
      (node (ref "P6") (pin "4") (pinfunction "4_4") (pintype "passive"))
      (node (ref "U14") (pin "15") (pinfunction "QA_15") (pintype "passive"))
    )
    (net (code "38") (name "/EN_1_C4") (class "Default")
      (node (ref "P8") (pin "4") (pinfunction "4_4") (pintype "passive"))
      (node (ref "U14") (pin "4") (pinfunction "QE_4") (pintype "passive"))
    )
    (net (code "39") (name "/EN_1_C5") (class "Default")
      (node (ref "P10") (pin "4") (pinfunction "4_4") (pintype "passive"))
      (node (ref "U15") (pin "15") (pinfunction "QA_15") (pintype "passive"))
    )
    (net (code "40") (name "/EN_1_C6") (class "Default")
      (node (ref "P12") (pin "4") (pinfunction "4_4") (pintype "passive"))
      (node (ref "U15") (pin "4") (pinfunction "QE_4") (pintype "passive"))
    )
    (net (code "41") (name "/EN_2_C1") (class "Default")
      (node (ref "P2") (pin "3") (pinfunction "3_3") (pintype "passive"))
      (node (ref "U5") (pin "1") (pinfunction "QB_1") (pintype "passive"))
    )
    (net (code "42") (name "/EN_2_C2") (class "Default")
      (node (ref "P4") (pin "3") (pinfunction "3_3") (pintype "passive"))
      (node (ref "U5") (pin "5") (pinfunction "QF_5") (pintype "passive"))
    )
    (net (code "43") (name "/EN_2_C3") (class "Default")
      (node (ref "P6") (pin "3") (pinfunction "3_3") (pintype "passive"))
      (node (ref "U14") (pin "1") (pinfunction "QB_1") (pintype "passive"))
    )
    (net (code "44") (name "/EN_2_C4") (class "Default")
      (node (ref "P8") (pin "3") (pinfunction "3_3") (pintype "passive"))
      (node (ref "U14") (pin "5") (pinfunction "QF_5") (pintype "passive"))
    )
    (net (code "45") (name "/EN_2_C5") (class "Default")
      (node (ref "P10") (pin "3") (pinfunction "3_3") (pintype "passive"))
      (node (ref "U15") (pin "1") (pinfunction "QB_1") (pintype "passive"))
    )
    (net (code "46") (name "/EN_2_C6") (class "Default")
      (node (ref "P12") (pin "3") (pinfunction "3_3") (pintype "passive"))
      (node (ref "U15") (pin "5") (pinfunction "QF_5") (pintype "passive"))
    )
    (net (code "47") (name "/EN_3_C1") (class "Default")
      (node (ref "P2") (pin "2") (pinfunction "2_2") (pintype "passive"))
      (node (ref "U5") (pin "2") (pinfunction "QC_2") (pintype "passive"))
    )
    (net (code "48") (name "/EN_3_C2") (class "Default")
      (node (ref "P4") (pin "2") (pinfunction "2_2") (pintype "passive"))
      (node (ref "U5") (pin "6") (pinfunction "QG_6") (pintype "passive"))
    )
    (net (code "49") (name "/EN_3_C3") (class "Default")
      (node (ref "P6") (pin "2") (pinfunction "2_2") (pintype "passive"))
      (node (ref "U14") (pin "2") (pinfunction "QC_2") (pintype "passive"))
    )
    (net (code "50") (name "/EN_3_C4") (class "Default")
      (node (ref "P8") (pin "2") (pinfunction "2_2") (pintype "passive"))
      (node (ref "U14") (pin "6") (pinfunction "QG_6") (pintype "passive"))
    )
    (net (code "51") (name "/EN_3_C5") (class "Default")
      (node (ref "P10") (pin "2") (pinfunction "2_2") (pintype "passive"))
      (node (ref "U15") (pin "2") (pinfunction "QC_2") (pintype "passive"))
    )
    (net (code "52") (name "/EN_3_C6") (class "Default")
      (node (ref "P12") (pin "2") (pinfunction "2_2") (pintype "passive"))
      (node (ref "U15") (pin "6") (pinfunction "QG_6") (pintype "passive"))
    )
    (net (code "53") (name "/EN_4_C1") (class "Default")
      (node (ref "P2") (pin "1") (pinfunction "1_1") (pintype "passive"))
      (node (ref "U5") (pin "3") (pinfunction "QD_3") (pintype "passive"))
    )
    (net (code "54") (name "/EN_4_C2") (class "Default")
      (node (ref "P4") (pin "1") (pinfunction "1_1") (pintype "passive"))
      (node (ref "U5") (pin "7") (pinfunction "QH_7") (pintype "passive"))
    )
    (net (code "55") (name "/EN_4_C3") (class "Default")
      (node (ref "P6") (pin "1") (pinfunction "1_1") (pintype "passive"))
      (node (ref "U14") (pin "3") (pinfunction "QD_3") (pintype "passive"))
    )
    (net (code "56") (name "/EN_4_C4") (class "Default")
      (node (ref "P8") (pin "1") (pinfunction "1_1") (pintype "passive"))
      (node (ref "U14") (pin "7") (pinfunction "QH_7") (pintype "passive"))
    )
    (net (code "57") (name "/EN_4_C5") (class "Default")
      (node (ref "P10") (pin "1") (pinfunction "1_1") (pintype "passive"))
      (node (ref "U15") (pin "3") (pinfunction "QD_3") (pintype "passive"))
    )
    (net (code "58") (name "/EN_4_C6") (class "Default")
      (node (ref "P12") (pin "1") (pinfunction "1_1") (pintype "passive"))
      (node (ref "U15") (pin "7") (pinfunction "QH_7") (pintype "passive"))
    )
    (net (code "59") (name "/EN_D1") (class "Default")
      (node (ref "U5") (pin "14") (pinfunction "SER_14") (pintype "passive"))
      (node (ref "U6") (pin "28") (pinfunction "PB15_28") (pintype "bidirectional"))
    )
    (net (code "60") (name "/ISP_RXD") (class "Default")
      (node (ref "P18") (pin "4") (pinfunction "4_4") (pintype "passive"))
      (node (ref "R18") (pin "1") (pinfunction "1_1") (pintype "passive"))
      (node (ref "U3") (pin "6") (pinfunction "6_6") (pintype "passive"))
    )
    (net (code "61") (name "/ISP_TXD") (class "Default")
      (node (ref "P18") (pin "3") (pinfunction "3_3") (pintype "passive"))
      (node (ref "R19") (pin "1") (pinfunction "1_1") (pintype "passive"))
      (node (ref "U3") (pin "4") (pinfunction "4_4") (pintype "passive"))
    )
    (net (code "62") (name "/I_AD") (class "Default")
      (node (ref "C44") (pin "2") (pinfunction "2_2") (pintype "passive"))
      (node (ref "U6") (pin "10") (pinfunction "PA0-WKUP_10") (pintype "bidirectional"))
      (node (ref "U7") (pin "3") (pinfunction "X_3") (pintype "passive"))
    )
    (net (code "63") (name "/I_OUT1") (class "Default")
      (node (ref "P1") (pin "3") (pinfunction "3_3") (pintype "passive"))
      (node (ref "U7") (pin "13") (pinfunction "X0_13") (pintype "passive"))
    )
    (net (code "64") (name "/I_OUT2") (class "Default")
      (node (ref "P3") (pin "3") (pinfunction "3_3") (pintype "passive"))
      (node (ref "U7") (pin "14") (pinfunction "X1_14") (pintype "passive"))
    )
    (net (code "65") (name "/I_OUT3") (class "Default")
      (node (ref "P5") (pin "3") (pinfunction "3_3") (pintype "passive"))
      (node (ref "U7") (pin "15") (pinfunction "X2_15") (pintype "passive"))
    )
    (net (code "66") (name "/I_OUT4") (class "Default")
      (node (ref "P7") (pin "3") (pinfunction "3_3") (pintype "passive"))
      (node (ref "U7") (pin "12") (pinfunction "X3_12") (pintype "passive"))
    )
    (net (code "67") (name "/I_OUT5") (class "Default")
      (node (ref "P9") (pin "3") (pinfunction "3_3") (pintype "passive"))
      (node (ref "U7") (pin "1") (pinfunction "X4_1") (pintype "passive"))
    )
    (net (code "68") (name "/I_OUT6") (class "Default")
      (node (ref "P11") (pin "3") (pinfunction "3_3") (pintype "passive"))
      (node (ref "U7") (pin "5") (pinfunction "X5_5") (pintype "passive"))
    )
    (net (code "69") (name "/KEY_1") (class "Default")
      (node (ref "C38") (pin "2") (pinfunction "2_2") (pintype "passive"))
      (node (ref "R36") (pin "1") (pinfunction "1_1") (pintype "passive"))
      (node (ref "R40") (pin "1") (pinfunction "1_1") (pintype "passive"))
      (node (ref "U6") (pin "4") (pinfunction "PC15-OSC32_OUT_4") (pintype "bidirectional"))
    )
    (net (code "70") (name "/KEY_2") (class "Default")
      (node (ref "C39") (pin "2") (pinfunction "2_2") (pintype "passive"))
      (node (ref "R37") (pin "1") (pinfunction "1_1") (pintype "passive"))
      (node (ref "R41") (pin "1") (pinfunction "1_1") (pintype "passive"))
      (node (ref "U6") (pin "3") (pinfunction "PC14-OSC32_IN_3") (pintype "bidirectional"))
    )
    (net (code "71") (name "/KEY_3") (class "Default")
      (node (ref "C40") (pin "2") (pinfunction "2_2") (pintype "passive"))
      (node (ref "R38") (pin "1") (pinfunction "1_1") (pintype "passive"))
      (node (ref "R42") (pin "1") (pinfunction "1_1") (pintype "passive"))
      (node (ref "U6") (pin "2") (pinfunction "PC13-TAMPER-RTC_2") (pintype "bidirectional"))
    )
    (net (code "72") (name "/KEY_10") (class "Default")
      (node (ref "P22") (pin "2") (pinfunction "2_2") (pintype "passive"))
      (node (ref "R36") (pin "2") (pinfunction "2_2") (pintype "passive"))
      (node (ref "S1") (pin "3") (pinfunction "3_3") (pintype "passive"))
      (node (ref "S1") (pin "4") (pinfunction "4_4") (pintype "passive"))
    )
    (net (code "73") (name "/KEY_20") (class "Default")
      (node (ref "P22") (pin "3") (pinfunction "3_3") (pintype "passive"))
      (node (ref "R37") (pin "2") (pinfunction "2_2") (pintype "passive"))
      (node (ref "S2") (pin "3") (pinfunction "3_3") (pintype "passive"))
      (node (ref "S2") (pin "4") (pinfunction "4_4") (pintype "passive"))
    )
    (net (code "74") (name "/KEY_30") (class "Default")
      (node (ref "P13") (pin "2") (pinfunction "2_2") (pintype "passive"))
      (node (ref "P22") (pin "4") (pinfunction "4_4") (pintype "passive"))
      (node (ref "R38") (pin "2") (pinfunction "2_2") (pintype "passive"))
      (node (ref "S3") (pin "3") (pinfunction "3_3") (pintype "passive"))
      (node (ref "S3") (pin "4") (pinfunction "4_4") (pintype "passive"))
    )
    (net (code "75") (name "/LCD_RXD") (class "Default")
      (node (ref "P24") (pin "2") (pinfunction "2_2") (pintype "passive"))
      (node (ref "R49") (pin "1") (pinfunction "1_1") (pintype "passive"))
      (node (ref "R50") (pin "1") (pinfunction "1_1") (pintype "passive"))
    )
    (net (code "76") (name "/LCD_TXD") (class "Default")
      (node (ref "P24") (pin "3") (pinfunction "3_3") (pintype "passive"))
      (node (ref "R47") (pin "1") (pinfunction "1_1") (pintype "passive"))
    )
    (net (code "77") (name "/LED_CON") (class "Default")
      (node (ref "R30") (pin "1") (pinfunction "1_1") (pintype "passive"))
      (node (ref "U6") (pin "19") (pinfunction "PB1_19") (pintype "bidirectional"))
    )
    (net (code "78") (name "/LIGHT_CHECK") (class "Default")
      (node (ref "C37") (pin "1") (pinfunction "1_1") (pintype "passive"))
      (node (ref "D3") (pin "1") (pinfunction "A_1") (pintype "passive"))
      (node (ref "P25") (pin "2") (pinfunction "2_2") (pintype "passive"))
      (node (ref "R9") (pin "1") (pinfunction "1_1") (pintype "passive"))
      (node (ref "U6") (pin "18") (pinfunction "PB0_18") (pintype "bidirectional"))
    )
    (net (code "79") (name "/MCU_RX1") (class "Default")
      (node (ref "R19") (pin "2") (pinfunction "2_2") (pintype "passive"))
      (node (ref "U22") (pin "13") (pinfunction "X_13") (pintype "passive"))
      (node (ref "U6") (pin "31") (pinfunction "PA10_31") (pintype "bidirectional"))
    )
    (net (code "80") (name "/MCU_RX2") (class "Default")
      (node (ref "R47") (pin "2") (pinfunction "2_2") (pintype "passive"))
      (node (ref "R48") (pin "2") (pinfunction "2_2") (pintype "passive"))
      (node (ref "U6") (pin "13") (pinfunction "PA3_13") (pintype "bidirectional"))
    )
    (net (code "81") (name "/MCU_RX3") (class "Default")
      (node (ref "R44") (pin "2") (pinfunction "2_2") (pintype "passive"))
      (node (ref "R45") (pin "2") (pinfunction "2_2") (pintype "passive"))
      (node (ref "U6") (pin "22") (pinfunction "PB11_22") (pintype "bidirectional"))
    )
    (net (code "82") (name "/MCU_TX1") (class "Default")
      (node (ref "R18") (pin "2") (pinfunction "2_2") (pintype "passive"))
      (node (ref "U22") (pin "3") (pinfunction "Y_3") (pintype "passive"))
      (node (ref "U6") (pin "30") (pinfunction "PA9_30") (pintype "bidirectional"))
    )
    (net (code "83") (name "/MCU_TX2") (class "Default")
      (node (ref "R50") (pin "2") (pinfunction "2_2") (pintype "passive"))
      (node (ref "U6") (pin "12") (pinfunction "PA2_12") (pintype "bidirectional"))
    )
    (net (code "84") (name "/MCU_TX3") (class "Default")
      (node (ref "R51") (pin "2") (pinfunction "2_2") (pintype "passive"))
      (node (ref "U6") (pin "21") (pinfunction "PB10_21") (pintype "bidirectional"))
    )
    (net (code "85") (name "/MOTOR_BACK") (class "Default")
      (node (ref "R22") (pin "1") (pinfunction "1_1") (pintype "passive"))
      (node (ref "U6") (pin "41") (pinfunction "PB5_41") (pintype "bidirectional"))
    )
    (net (code "86") (name "/MOTOR_FORW") (class "Default")
      (node (ref "R23") (pin "2") (pinfunction "2_2") (pintype "passive"))
      (node (ref "U6") (pin "40") (pinfunction "PB4/JNTRST_40") (pintype "bidirectional"))
    )
    (net (code "87") (name "/NRST") (class "Default")
      (node (ref "C26") (pin "1") (pinfunction "1_1") (pintype "passive"))
      (node (ref "R12") (pin "1") (pinfunction "1_1") (pintype "passive"))
      (node (ref "S0") (pin "1") (pinfunction "1_1") (pintype "passive"))
      (node (ref "S0") (pin "2") (pinfunction "2_2") (pintype "passive"))
      (node (ref "U6") (pin "7") (pinfunction "NRST_7") (pintype "bidirectional"))
    )
    (net (code "88") (name "/O2_OUT") (class "Default")
      (node (ref "R75") (pin "1") (pinfunction "1_1") (pintype "passive"))
      (node (ref "U20") (pin "3") (pinfunction "X_3") (pintype "passive"))
    )
    (net (code "89") (name "/O2_OUT1") (class "Default")
      (node (ref "P2") (pin "8") (pinfunction "8_8") (pintype "passive"))
      (node (ref "U20") (pin "13") (pinfunction "X0_13") (pintype "passive"))
    )
    (net (code "90") (name "/O2_OUT2") (class "Default")
      (node (ref "P4") (pin "8") (pinfunction "8_8") (pintype "passive"))
      (node (ref "U20") (pin "14") (pinfunction "X1_14") (pintype "passive"))
    )
    (net (code "91") (name "/O2_OUT3") (class "Default")
      (node (ref "P6") (pin "8") (pinfunction "8_8") (pintype "passive"))
      (node (ref "U20") (pin "15") (pinfunction "X2_15") (pintype "passive"))
    )
    (net (code "92") (name "/O2_OUT4") (class "Default")
      (node (ref "P8") (pin "8") (pinfunction "8_8") (pintype "passive"))
      (node (ref "U20") (pin "12") (pinfunction "X3_12") (pintype "passive"))
    )
    (net (code "93") (name "/O2_OUT5") (class "Default")
      (node (ref "P10") (pin "8") (pinfunction "8_8") (pintype "passive"))
      (node (ref "U20") (pin "1") (pinfunction "X4_1") (pintype "passive"))
    )
    (net (code "94") (name "/O2_OUT6") (class "Default")
      (node (ref "P12") (pin "8") (pinfunction "8_8") (pintype "passive"))
      (node (ref "U20") (pin "5") (pinfunction "X5_5") (pintype "passive"))
    )
    (net (code "95") (name "/OSC_IN") (class "Default")
      (node (ref "C24") (pin "1") (pinfunction "1_1") (pintype "passive"))
      (node (ref "R11") (pin "1") (pinfunction "1_1") (pintype "passive"))
      (node (ref "U6") (pin "5") (pinfunction "OSC_IN/PD0_5") (pintype "input"))
      (node (ref "Y1") (pin "3") (pinfunction "OUTPUT_3") (pintype "passive"))
    )
    (net (code "96") (name "/OSC_OUT") (class "Default")
      (node (ref "C25") (pin "1") (pinfunction "1_1") (pintype "passive"))
      (node (ref "R11") (pin "2") (pinfunction "2_2") (pintype "passive"))
      (node (ref "U6") (pin "6") (pinfunction "OSC_OUT/PD1_6") (pintype "output"))
      (node (ref "Y1") (pin "1") (pinfunction "INPUT_1") (pintype "passive"))
    )
    (net (code "97") (name "/O_OUT") (class "Default")
      (node (ref "R66") (pin "1") (pinfunction "1_1") (pintype "passive"))
      (node (ref "U17") (pin "3") (pinfunction "X_3") (pintype "passive"))
    )
    (net (code "98") (name "/O_OUT1") (class "Default")
      (node (ref "P1") (pin "8") (pinfunction "8_8") (pintype "passive"))
      (node (ref "U17") (pin "13") (pinfunction "X0_13") (pintype "passive"))
    )
    (net (code "99") (name "/O_OUT2") (class "Default")
      (node (ref "P3") (pin "8") (pinfunction "8_8") (pintype "passive"))
      (node (ref "U17") (pin "14") (pinfunction "X1_14") (pintype "passive"))
    )
    (net (code "100") (name "/O_OUT3") (class "Default")
      (node (ref "P5") (pin "8") (pinfunction "8_8") (pintype "passive"))
      (node (ref "U17") (pin "15") (pinfunction "X2_15") (pintype "passive"))
    )
    (net (code "101") (name "/O_OUT4") (class "Default")
      (node (ref "P7") (pin "8") (pinfunction "8_8") (pintype "passive"))
      (node (ref "U17") (pin "12") (pinfunction "X3_12") (pintype "passive"))
    )
    (net (code "102") (name "/O_OUT5") (class "Default")
      (node (ref "P9") (pin "8") (pinfunction "8_8") (pintype "passive"))
      (node (ref "U17") (pin "1") (pinfunction "X4_1") (pintype "passive"))
    )
    (net (code "103") (name "/O_OUT6") (class "Default")
      (node (ref "P11") (pin "8") (pinfunction "8_8") (pintype "passive"))
      (node (ref "U17") (pin "5") (pinfunction "X5_5") (pintype "passive"))
    )
    (net (code "104") (name "/PRT_DTR") (class "Default")
      (node (ref "R43") (pin "2") (pinfunction "2_2") (pintype "passive"))
      (node (ref "U6") (pin "42") (pinfunction "PB6_42") (pintype "bidirectional"))
    )
    (net (code "105") (name "/PRT_RXD") (class "Default")
      (node (ref "P23") (pin "4") (pinfunction "4_4") (pintype "passive"))
      (node (ref "R51") (pin "1") (pinfunction "1_1") (pintype "passive"))
    )
    (net (code "106") (name "/PRT_TXD") (class "Default")
      (node (ref "P23") (pin "3") (pinfunction "3_3") (pintype "passive"))
      (node (ref "R44") (pin "1") (pinfunction "1_1") (pintype "passive"))
    )
    (net (code "107") (name "/QH1'") (class "Default")
      (node (ref "U14") (pin "14") (pinfunction "SER_14") (pintype "passive"))
      (node (ref "U5") (pin "9") (pinfunction "QH'_9") (pintype "passive"))
    )
    (net (code "108") (name "/QH2'") (class "Default")
      (node (ref "U14") (pin "9") (pinfunction "QH'_9") (pintype "passive"))
      (node (ref "U15") (pin "14") (pinfunction "SER_14") (pintype "passive"))
    )
    (net (code "109") (name "/RCLK_1") (class "Default")
      (node (ref "U14") (pin "12") (pinfunction "RCLK_12") (pintype "passive"))
      (node (ref "U15") (pin "12") (pinfunction "RCLK_12") (pintype "passive"))
      (node (ref "U5") (pin "12") (pinfunction "RCLK_12") (pintype "passive"))
      (node (ref "U6") (pin "29") (pinfunction "PA8_29") (pintype "bidirectional"))
    )
    (net (code "110") (name "/ROW_A") (class "Default")
      (node (ref "P10") (pin "5") (pinfunction "5_5") (pintype "passive"))
      (node (ref "P12") (pin "5") (pinfunction "5_5") (pintype "passive"))
      (node (ref "P2") (pin "5") (pinfunction "5_5") (pintype "passive"))
      (node (ref "P4") (pin "5") (pinfunction "5_5") (pintype "passive"))
      (node (ref "P6") (pin "5") (pinfunction "5_5") (pintype "passive"))
      (node (ref "P8") (pin "5") (pinfunction "5_5") (pintype "passive"))
      (node (ref "R59") (pin "1") (pinfunction "1_1") (pintype "passive"))
    )
    (net (code "111") (name "/ROW_B") (class "Default")
      (node (ref "P10") (pin "6") (pinfunction "6_6") (pintype "passive"))
      (node (ref "P12") (pin "6") (pinfunction "6_6") (pintype "passive"))
      (node (ref "P2") (pin "6") (pinfunction "6_6") (pintype "passive"))
      (node (ref "P4") (pin "6") (pinfunction "6_6") (pintype "passive"))
      (node (ref "P6") (pin "6") (pinfunction "6_6") (pintype "passive"))
      (node (ref "P8") (pin "6") (pinfunction "6_6") (pintype "passive"))
      (node (ref "R60") (pin "1") (pinfunction "1_1") (pintype "passive"))
    )
    (net (code "112") (name "/RTX_CTL") (class "Default")
      (node (ref "U22") (pin "10") (pinfunction "A_10") (pintype "passive"))
      (node (ref "U6") (pin "39") (pinfunction "PB3/JTDO_39") (pintype "bidirectional"))
    )
    (net (code "113") (name "/RX_OUT") (class "Default")
      (node (ref "U22") (pin "1") (pinfunction "Y0_1") (pintype "passive"))
      (node (ref "U22") (pin "14") (pinfunction "X1_14") (pintype "passive"))
      (node (ref "U8") (pin "3") (pinfunction "X_3") (pintype "passive"))
    )
    (net (code "114") (name "/RX_OUT1") (class "Default")
      (node (ref "P1") (pin "4") (pinfunction "4_4") (pintype "passive"))
      (node (ref "U8") (pin "13") (pinfunction "X0_13") (pintype "passive"))
    )
    (net (code "115") (name "/RX_OUT2") (class "Default")
      (node (ref "P3") (pin "4") (pinfunction "4_4") (pintype "passive"))
      (node (ref "U8") (pin "14") (pinfunction "X1_14") (pintype "passive"))
    )
    (net (code "116") (name "/RX_OUT3") (class "Default")
      (node (ref "P5") (pin "4") (pinfunction "4_4") (pintype "passive"))
      (node (ref "U8") (pin "15") (pinfunction "X2_15") (pintype "passive"))
    )
    (net (code "117") (name "/RX_OUT4") (class "Default")
      (node (ref "P7") (pin "4") (pinfunction "4_4") (pintype "passive"))
      (node (ref "U8") (pin "12") (pinfunction "X3_12") (pintype "passive"))
    )
    (net (code "118") (name "/RX_OUT5") (class "Default")
      (node (ref "P9") (pin "4") (pinfunction "4_4") (pintype "passive"))
      (node (ref "U8") (pin "1") (pinfunction "X4_1") (pintype "passive"))
    )
    (net (code "119") (name "/RX_OUT6") (class "Default")
      (node (ref "P11") (pin "4") (pinfunction "4_4") (pintype "passive"))
      (node (ref "U8") (pin "5") (pinfunction "X5_5") (pintype "passive"))
    )
    (net (code "120") (name "/SRCLK_1") (class "Default")
      (node (ref "U14") (pin "11") (pinfunction "SRCLK_11") (pintype "passive"))
      (node (ref "U15") (pin "11") (pinfunction "SRCLK_11") (pintype "passive"))
      (node (ref "U5") (pin "11") (pinfunction "SRCLK_11") (pintype "passive"))
      (node (ref "U6") (pin "27") (pinfunction "PB14_27") (pintype "bidirectional"))
    )
    (net (code "121") (name "/SWCLK") (class "Default")
      (node (ref "P17") (pin "4") (pinfunction "4_4") (pintype "passive"))
      (node (ref "U3") (pin "1") (pinfunction "1_1") (pintype "passive"))
      (node (ref "U6") (pin "37") (pinfunction "PA14/JTCK/SWCLK_37") (pintype "bidirectional"))
    )
    (net (code "122") (name "/SWDIO") (class "Default")
      (node (ref "P17") (pin "3") (pinfunction "3_3") (pintype "passive"))
      (node (ref "U3") (pin "3") (pinfunction "3_3") (pintype "passive"))
      (node (ref "U6") (pin "34") (pinfunction "PA13/JTMS/SWDIO_34") (pintype "bidirectional"))
    )
    (net (code "123") (name "/TX_OUT") (class "Default")
      (node (ref "U12") (pin "3") (pinfunction "X_3") (pintype "passive"))
      (node (ref "U22") (pin "12") (pinfunction "X0_12") (pintype "passive"))
      (node (ref "U22") (pin "5") (pinfunction "Y1_5") (pintype "passive"))
    )
    (net (code "124") (name "/TX_OUT1") (class "Default")
      (node (ref "P1") (pin "7") (pinfunction "7_7") (pintype "passive"))
      (node (ref "U12") (pin "13") (pinfunction "X0_13") (pintype "passive"))
    )
    (net (code "125") (name "/TX_OUT2") (class "Default")
      (node (ref "P3") (pin "7") (pinfunction "7_7") (pintype "passive"))
      (node (ref "U12") (pin "14") (pinfunction "X1_14") (pintype "passive"))
    )
    (net (code "126") (name "/TX_OUT3") (class "Default")
      (node (ref "P5") (pin "7") (pinfunction "7_7") (pintype "passive"))
      (node (ref "U12") (pin "15") (pinfunction "X2_15") (pintype "passive"))
    )
    (net (code "127") (name "/TX_OUT4") (class "Default")
      (node (ref "P7") (pin "7") (pinfunction "7_7") (pintype "passive"))
      (node (ref "U12") (pin "12") (pinfunction "X3_12") (pintype "passive"))
    )
    (net (code "128") (name "/TX_OUT5") (class "Default")
      (node (ref "P9") (pin "7") (pinfunction "7_7") (pintype "passive"))
      (node (ref "U12") (pin "1") (pinfunction "X4_1") (pintype "passive"))
    )
    (net (code "129") (name "/TX_OUT6") (class "Default")
      (node (ref "P11") (pin "7") (pinfunction "7_7") (pintype "passive"))
      (node (ref "U12") (pin "5") (pinfunction "X5_5") (pintype "passive"))
    )
    (net (code "130") (name "3.3V") (class "Default")
      (node (ref "C10") (pin "1") (pinfunction "1_1") (pintype "passive"))
      (node (ref "C16") (pin "1") (pinfunction "1_1") (pintype "passive"))
      (node (ref "C30") (pin "1") (pinfunction "1_1") (pintype "passive"))
      (node (ref "C34") (pin "1") (pinfunction "1_1") (pintype "passive"))
      (node (ref "C35") (pin "1") (pinfunction "1_1") (pintype "passive"))
      (node (ref "C36") (pin "1") (pinfunction "1_1") (pintype "passive"))
      (node (ref "C41") (pin "1") (pinfunction "1_1") (pintype "passive"))
      (node (ref "C42") (pin "1") (pinfunction "1_1") (pintype "passive"))
      (node (ref "C43") (pin "1") (pinfunction "1_1") (pintype "passive"))
      (node (ref "C46") (pin "1") (pinfunction "1_1") (pintype "passive"))
      (node (ref "C55") (pin "1") (pinfunction "1_1") (pintype "passive"))
      (node (ref "C56") (pin "1") (pinfunction "1_1") (pintype "passive"))
      (node (ref "C57") (pin "1") (pinfunction "1_1") (pintype "passive"))
      (node (ref "C6") (pin "1") (pinfunction "1_1") (pintype "passive"))
      (node (ref "C60") (pin "1") (pinfunction "1_1") (pintype "passive"))
      (node (ref "C61") (pin "1") (pinfunction "1_1") (pintype "passive"))
      (node (ref "C63") (pin "2") (pinfunction "2_2") (pintype "passive"))
      (node (ref "C7") (pin "1") (pinfunction "1_1") (pintype "passive"))
      (node (ref "C8") (pin "1") (pinfunction "1_1") (pintype "passive"))
      (node (ref "C9") (pin "1") (pinfunction "1_1") (pintype "passive"))
      (node (ref "D3") (pin "2") (pinfunction "K_2") (pintype "passive"))
      (node (ref "LS1") (pin "1") (pinfunction "1_1") (pintype "passive"))
      (node (ref "P17") (pin "1") (pinfunction "1_1") (pintype "passive"))
      (node (ref "P18") (pin "1") (pinfunction "1_1") (pintype "passive"))
      (node (ref "P25") (pin "1") (pinfunction "1_1") (pintype "passive"))
      (node (ref "R12") (pin "2") (pinfunction "2_2") (pintype "passive"))
      (node (ref "R15") (pin "2") (pinfunction "2_2") (pintype "passive"))
      (node (ref "R24") (pin "1") (pinfunction "1_1") (pintype "passive"))
      (node (ref "R25") (pin "1") (pinfunction "1_1") (pintype "passive"))
      (node (ref "R3") (pin "1") (pinfunction "1_1") (pintype "passive"))
      (node (ref "R67") (pin "1") (pinfunction "1_1") (pintype "passive"))
      (node (ref "R68") (pin "1") (pinfunction "1_1") (pintype "passive"))
      (node (ref "R69") (pin "1") (pinfunction "1_1") (pintype "passive"))
      (node (ref "S1") (pin "1") (pinfunction "1_1") (pintype "passive"))
      (node (ref "S1") (pin "2") (pinfunction "2_2") (pintype "passive"))
      (node (ref "S2") (pin "1") (pinfunction "1_1") (pintype "passive"))
      (node (ref "S2") (pin "2") (pinfunction "2_2") (pintype "passive"))
      (node (ref "S3") (pin "1") (pinfunction "1_1") (pintype "passive"))
      (node (ref "S3") (pin "2") (pinfunction "2_2") (pintype "passive"))
      (node (ref "U10") (pin "16") (pinfunction "VCC_16") (pintype "passive"))
      (node (ref "U11") (pin "16") (pinfunction "VCC_16") (pintype "passive"))
      (node (ref "U12") (pin "16") (pinfunction "VCC_16") (pintype "passive"))
      (node (ref "U13") (pin "8") (pinfunction "Vcc+_8") (pintype "passive"))
      (node (ref "U14") (pin "16") (pinfunction "VCC_16") (pintype "passive"))
      (node (ref "U15") (pin "16") (pinfunction "VCC_16") (pintype "passive"))
      (node (ref "U17") (pin "16") (pinfunction "VCC_16") (pintype "passive"))
      (node (ref "U20") (pin "16") (pinfunction "VCC_16") (pintype "passive"))
      (node (ref "U21") (pin "16") (pinfunction "VCC_16") (pintype "passive"))
      (node (ref "U22") (pin "16") (pinfunction "VDD_16") (pintype "passive"))
      (node (ref "U3") (pin "5") (pinfunction "5_5") (pintype "passive"))
      (node (ref "U4") (pin "3") (pinfunction "VOUT_3") (pintype "passive"))
      (node (ref "U5") (pin "16") (pinfunction "VCC_16") (pintype "passive"))
      (node (ref "U6") (pin "1") (pinfunction "VBAT_1") (pintype "power_in"))
      (node (ref "U6") (pin "24") (pinfunction "VDD_1_24") (pintype "power_in"))
      (node (ref "U6") (pin "36") (pinfunction "VDD_2_36") (pintype "power_in"))
      (node (ref "U6") (pin "48") (pinfunction "VDD_3_48") (pintype "power_in"))
      (node (ref "U7") (pin "16") (pinfunction "VCC_16") (pintype "passive"))
      (node (ref "U8") (pin "16") (pinfunction "VCC_16") (pintype "passive"))
    )
    (net (code "131") (name "6V_1") (class "Default")
      (node (ref "C19") (pin "1") (pinfunction "1_1") (pintype "passive"))
      (node (ref "C20") (pin "1") (pinfunction "1_1") (pintype "passive"))
      (node (ref "D4") (pin "1") (pinfunction "A_1") (pintype "passive"))
      (node (ref "D5") (pin "1") (pinfunction "A_1") (pintype "passive"))
      (node (ref "D6") (pin "1") (pinfunction "A_1") (pintype "passive"))
      (node (ref "L3") (pin "2") (pinfunction "2_2") (pintype "passive"))
      (node (ref "R5") (pin "2") (pinfunction "2_2") (pintype "passive"))
      (node (ref "U9") (pin "4") (pinfunction "VCC_4") (pintype "passive"))
    )
    (net (code "132") (name "8V") (class "Default")
      (node (ref "C52") (pin "1") (pinfunction "1_1") (pintype "passive"))
      (node (ref "C53") (pin "1") (pinfunction "1_1") (pintype "passive"))
      (node (ref "L4") (pin "2") (pinfunction "2_2") (pintype "passive"))
      (node (ref "P23") (pin "1") (pinfunction "1_1") (pintype "passive"))
      (node (ref "R8") (pin "2") (pinfunction "2_2") (pintype "passive"))
    )
    (net (code "133") (name "12V") (class "Default")
      (node (ref "C13") (pin "2") (pinfunction "2_2") (pintype "passive"))
      (node (ref "C14") (pin "1") (pinfunction "1_1") (pintype "passive"))
      (node (ref "C2") (pin "1") (pinfunction "1_1") (pintype "passive"))
      (node (ref "C29") (pin "1") (pinfunction "1_1") (pintype "passive"))
      (node (ref "C3") (pin "1") (pinfunction "1_1") (pintype "passive"))
      (node (ref "C4") (pin "1") (pinfunction "1_1") (pintype "passive"))
      (node (ref "C48") (pin "1") (pinfunction "1_1") (pintype "passive"))
      (node (ref "L1") (pin "1") (pinfunction "1_1") (pintype "passive"))
      (node (ref "L5") (pin "1") (pinfunction "1_1") (pintype "passive"))
      (node (ref "Q2") (pin "2") (pinfunction "S_2") (pintype "passive"))
      (node (ref "Q3") (pin "2") (pinfunction "S_2") (pintype "passive"))
      (node (ref "R1") (pin "2") (pinfunction "2_2") (pintype "passive"))
      (node (ref "R28") (pin "2") (pinfunction "2_2") (pintype "passive"))
      (node (ref "R32") (pin "2") (pinfunction "2_2") (pintype "passive"))
      (node (ref "R6") (pin "2") (pinfunction "2_2") (pintype "passive"))
      (node (ref "U1") (pin "2") (pinfunction "IN_2") (pintype "passive"))
      (node (ref "U2") (pin "2") (pinfunction "IN_2") (pintype "passive"))
    )
    (net (code "134") (name "GND") (class "Default")
      (node (ref "C10") (pin "2") (pinfunction "2_2") (pintype "passive"))
      (node (ref "C11") (pin "2") (pinfunction "2_2") (pintype "passive"))
      (node (ref "C13") (pin "1") (pinfunction "1_1") (pintype "passive"))
      (node (ref "C14") (pin "2") (pinfunction "2_2") (pintype "passive"))
      (node (ref "C16") (pin "2") (pinfunction "2_2") (pintype "passive"))
      (node (ref "C17") (pin "2") (pinfunction "2_2") (pintype "passive"))
      (node (ref "C19") (pin "2") (pinfunction "2_2") (pintype "passive"))
      (node (ref "C2") (pin "2") (pinfunction "2_2") (pintype "passive"))
      (node (ref "C20") (pin "2") (pinfunction "2_2") (pintype "passive"))
      (node (ref "C21") (pin "2") (pinfunction "2_2") (pintype "passive"))
      (node (ref "C22") (pin "2") (pinfunction "2_2") (pintype "passive"))
      (node (ref "C23") (pin "1") (pinfunction "1_1") (pintype "passive"))
      (node (ref "C24") (pin "2") (pinfunction "2_2") (pintype "passive"))
      (node (ref "C25") (pin "2") (pinfunction "2_2") (pintype "passive"))
      (node (ref "C26") (pin "2") (pinfunction "2_2") (pintype "passive"))
      (node (ref "C27") (pin "2") (pinfunction "2_2") (pintype "passive"))
      (node (ref "C29") (pin "2") (pinfunction "2_2") (pintype "passive"))
      (node (ref "C3") (pin "2") (pinfunction "2_2") (pintype "passive"))
      (node (ref "C30") (pin "2") (pinfunction "2_2") (pintype "passive"))
      (node (ref "C31") (pin "2") (pinfunction "2_2") (pintype "passive"))
      (node (ref "C32") (pin "1") (pinfunction "1_1") (pintype "passive"))
      (node (ref "C33") (pin "1") (pinfunction "1_1") (pintype "passive"))
      (node (ref "C34") (pin "2") (pinfunction "2_2") (pintype "passive"))
      (node (ref "C35") (pin "2") (pinfunction "2_2") (pintype "passive"))
      (node (ref "C36") (pin "2") (pinfunction "2_2") (pintype "passive"))
      (node (ref "C37") (pin "2") (pinfunction "2_2") (pintype "passive"))
      (node (ref "C38") (pin "1") (pinfunction "1_1") (pintype "passive"))
      (node (ref "C39") (pin "1") (pinfunction "1_1") (pintype "passive"))
      (node (ref "C4") (pin "2") (pinfunction "2_2") (pintype "passive"))
      (node (ref "C40") (pin "1") (pinfunction "1_1") (pintype "passive"))
      (node (ref "C41") (pin "2") (pinfunction "2_2") (pintype "passive"))
      (node (ref "C42") (pin "2") (pinfunction "2_2") (pintype "passive"))
      (node (ref "C43") (pin "2") (pinfunction "2_2") (pintype "passive"))
      (node (ref "C44") (pin "1") (pinfunction "1_1") (pintype "passive"))
      (node (ref "C45") (pin "2") (pinfunction "2_2") (pintype "passive"))
      (node (ref "C46") (pin "2") (pinfunction "2_2") (pintype "passive"))
      (node (ref "C47") (pin "1") (pinfunction "1_1") (pintype "passive"))
      (node (ref "C48") (pin "2") (pinfunction "2_2") (pintype "passive"))
      (node (ref "C5") (pin "2") (pinfunction "2_2") (pintype "passive"))
      (node (ref "C50") (pin "2") (pinfunction "2_2") (pintype "passive"))
      (node (ref "C52") (pin "2") (pinfunction "2_2") (pintype "passive"))
      (node (ref "C53") (pin "2") (pinfunction "2_2") (pintype "passive"))
      (node (ref "C55") (pin "2") (pinfunction "2_2") (pintype "passive"))
      (node (ref "C56") (pin "2") (pinfunction "2_2") (pintype "passive"))
      (node (ref "C57") (pin "2") (pinfunction "2_2") (pintype "passive"))
      (node (ref "C6") (pin "2") (pinfunction "2_2") (pintype "passive"))
      (node (ref "C60") (pin "2") (pinfunction "2_2") (pintype "passive"))
      (node (ref "C61") (pin "2") (pinfunction "2_2") (pintype "passive"))
      (node (ref "C63") (pin "1") (pinfunction "1_1") (pintype "passive"))
      (node (ref "C65") (pin "1") (pinfunction "1_1") (pintype "passive"))
      (node (ref "C7") (pin "2") (pinfunction "2_2") (pintype "passive"))
      (node (ref "C8") (pin "2") (pinfunction "2_2") (pintype "passive"))
      (node (ref "C9") (pin "2") (pinfunction "2_2") (pintype "passive"))
      (node (ref "D2") (pin "1") (pinfunction "A_1") (pintype "passive"))
      (node (ref "D7") (pin "1") (pinfunction "A_1") (pintype "passive"))
      (node (ref "D8") (pin "1") (pinfunction "A_1") (pintype "passive"))
      (node (ref "L2") (pin "1") (pinfunction "1_1") (pintype "passive"))
      (node (ref "LD0") (pin "2") (pinfunction "K_2") (pintype "passive"))
      (node (ref "P1") (pin "2") (pinfunction "2_2") (pintype "passive"))
      (node (ref "P11") (pin "2") (pinfunction "2_2") (pintype "passive"))
      (node (ref "P17") (pin "2") (pinfunction "2_2") (pintype "passive"))
      (node (ref "P18") (pin "2") (pinfunction "2_2") (pintype "passive"))
      (node (ref "P20") (pin "2") (pinfunction "2_2") (pintype "passive"))
      (node (ref "P21") (pin "2") (pinfunction "2_2") (pintype "passive"))
      (node (ref "P23") (pin "5") (pinfunction "5_5") (pintype "passive"))
      (node (ref "P24") (pin "4") (pinfunction "4_4") (pintype "passive"))
      (node (ref "P3") (pin "2") (pinfunction "2_2") (pintype "passive"))
      (node (ref "P5") (pin "2") (pinfunction "2_2") (pintype "passive"))
      (node (ref "P7") (pin "2") (pinfunction "2_2") (pintype "passive"))
      (node (ref "P9") (pin "2") (pinfunction "2_2") (pintype "passive"))
      (node (ref "Q5") (pin "2") (pinfunction "E_2") (pintype "passive"))
      (node (ref "Q6") (pin "2") (pinfunction "E_2") (pintype "passive"))
      (node (ref "Q7") (pin "2") (pinfunction "E_2") (pintype "passive"))
      (node (ref "R10") (pin "1") (pinfunction "1_1") (pintype "passive"))
      (node (ref "R14") (pin "1") (pinfunction "1_1") (pintype "passive"))
      (node (ref "R17") (pin "1") (pinfunction "1_1") (pintype "passive"))
      (node (ref "R2") (pin "1") (pinfunction "1_1") (pintype "passive"))
      (node (ref "R21") (pin "1") (pinfunction "1_1") (pintype "passive"))
      (node (ref "R27") (pin "1") (pinfunction "1_1") (pintype "passive"))
      (node (ref "R31") (pin "1") (pinfunction "1_1") (pintype "passive"))
      (node (ref "R4") (pin "1") (pinfunction "1_1") (pintype "passive"))
      (node (ref "R40") (pin "2") (pinfunction "2_2") (pintype "passive"))
      (node (ref "R41") (pin "2") (pinfunction "2_2") (pintype "passive"))
      (node (ref "R42") (pin "2") (pinfunction "2_2") (pintype "passive"))
      (node (ref "R45") (pin "1") (pinfunction "1_1") (pintype "passive"))
      (node (ref "R48") (pin "1") (pinfunction "1_1") (pintype "passive"))
      (node (ref "R52") (pin "2") (pinfunction "2_2") (pintype "passive"))
      (node (ref "R57") (pin "2") (pinfunction "2_2") (pintype "passive"))
      (node (ref "R63") (pin "2") (pinfunction "2_2") (pintype "passive"))
      (node (ref "R7") (pin "1") (pinfunction "1_1") (pintype "passive"))
      (node (ref "R70") (pin "1") (pinfunction "1_1") (pintype "passive"))
      (node (ref "R76") (pin "2") (pinfunction "2_2") (pintype "passive"))
      (node (ref "R78") (pin "1") (pinfunction "1_1") (pintype "passive"))
      (node (ref "R9") (pin "2") (pinfunction "2_2") (pintype "passive"))
      (node (ref "S0") (pin "3") (pinfunction "3_3") (pintype "passive"))
      (node (ref "S0") (pin "4") (pinfunction "4_4") (pintype "passive"))
      (node (ref "U1") (pin "4") (pinfunction "GND_4") (pintype "passive"))
      (node (ref "U1") (pin "9") (pinfunction "GND_9") (pintype "passive"))
      (node (ref "U10") (pin "6") (pinfunction "E_6") (pintype "passive"))
      (node (ref "U10") (pin "7") (pinfunction "VEE_7") (pintype "passive"))
      (node (ref "U10") (pin "8") (pinfunction "GND_8") (pintype "passive"))
      (node (ref "U11") (pin "6") (pinfunction "E_6") (pintype "passive"))
      (node (ref "U11") (pin "7") (pinfunction "VEE_7") (pintype "passive"))
      (node (ref "U11") (pin "8") (pinfunction "GND_8") (pintype "passive"))
      (node (ref "U12") (pin "6") (pinfunction "E_6") (pintype "passive"))
      (node (ref "U12") (pin "7") (pinfunction "VEE_7") (pintype "passive"))
      (node (ref "U12") (pin "8") (pinfunction "GND_8") (pintype "passive"))
      (node (ref "U13") (pin "4") (pinfunction "Vcc-_4") (pintype "passive"))
      (node (ref "U14") (pin "13") (pinfunction "/OE_13") (pintype "passive"))
      (node (ref "U14") (pin "8") (pinfunction "GND_8") (pintype "passive"))
      (node (ref "U15") (pin "13") (pinfunction "/OE_13") (pintype "passive"))
      (node (ref "U15") (pin "8") (pinfunction "GND_8") (pintype "passive"))
      (node (ref "U16") (pin "1") (pinfunction "GND_1") (pintype "passive"))
      (node (ref "U17") (pin "6") (pinfunction "E_6") (pintype "passive"))
      (node (ref "U17") (pin "7") (pinfunction "VEE_7") (pintype "passive"))
      (node (ref "U17") (pin "8") (pinfunction "GND_8") (pintype "passive"))
      (node (ref "U2") (pin "4") (pinfunction "GND_4") (pintype "passive"))
      (node (ref "U2") (pin "9") (pinfunction "GND_9") (pintype "passive"))
      (node (ref "U20") (pin "6") (pinfunction "E_6") (pintype "passive"))
      (node (ref "U20") (pin "7") (pinfunction "VEE_7") (pintype "passive"))
      (node (ref "U20") (pin "8") (pinfunction "GND_8") (pintype "passive"))
      (node (ref "U21") (pin "6") (pinfunction "E_6") (pintype "passive"))
      (node (ref "U21") (pin "7") (pinfunction "VEE_7") (pintype "passive"))
      (node (ref "U21") (pin "8") (pinfunction "GND_8") (pintype "passive"))
      (node (ref "U22") (pin "6") (pinfunction "INH_6") (pintype "passive"))
      (node (ref "U22") (pin "7") (pinfunction "VEE_7") (pintype "passive"))
      (node (ref "U22") (pin "8") (pinfunction "VSS_8") (pintype "passive"))
      (node (ref "U22") (pin "9") (pinfunction "B_9") (pintype "passive"))
      (node (ref "U3") (pin "2") (pinfunction "GND_2") (pintype "passive"))
      (node (ref "U4") (pin "1") (pinfunction "GND_1") (pintype "passive"))
      (node (ref "U5") (pin "13") (pinfunction "/OE_13") (pintype "passive"))
      (node (ref "U5") (pin "8") (pinfunction "GND_8") (pintype "passive"))
      (node (ref "U6") (pin "23") (pinfunction "VSS_1_23") (pintype "power_in"))
      (node (ref "U6") (pin "35") (pinfunction "VSS_2_35") (pintype "power_in"))
      (node (ref "U6") (pin "47") (pinfunction "VSS_3_47") (pintype "power_in"))
      (node (ref "U6") (pin "8") (pinfunction "VSSA_8") (pintype "power_in"))
      (node (ref "U7") (pin "6") (pinfunction "E_6") (pintype "passive"))
      (node (ref "U7") (pin "7") (pinfunction "VEE_7") (pintype "passive"))
      (node (ref "U7") (pin "8") (pinfunction "GND_8") (pintype "passive"))
      (node (ref "U8") (pin "6") (pinfunction "E_6") (pintype "passive"))
      (node (ref "U8") (pin "7") (pinfunction "VEE_7") (pintype "passive"))
      (node (ref "U8") (pin "8") (pinfunction "GND_8") (pintype "passive"))
      (node (ref "U9") (pin "3") (pinfunction "GND_3") (pintype "passive"))
    )
    (net (code "135") (name "Net-(C18-Pad2)") (class "Default")
      (node (ref "C18") (pin "2") (pinfunction "2_2") (pintype "passive"))
      (node (ref "R2") (pin "2") (pinfunction "2_2") (pintype "passive"))
    )
    (net (code "136") (name "Net-(C51-Pad2)") (class "Default")
      (node (ref "C51") (pin "2") (pinfunction "2_2") (pintype "passive"))
      (node (ref "R10") (pin "2") (pinfunction "2_2") (pintype "passive"))
    )
    (net (code "137") (name "Net-(C65-Pad2)") (class "Default")
      (node (ref "C65") (pin "2") (pinfunction "2_2") (pintype "passive"))
      (node (ref "R72") (pin "2") (pinfunction "2_2") (pintype "passive"))
      (node (ref "R78") (pin "2") (pinfunction "2_2") (pintype "passive"))
      (node (ref "R79") (pin "1") (pinfunction "1_1") (pintype "passive"))
    )
    (net (code "138") (name "Net-(D1-A)") (class "Default")
      (node (ref "D1") (pin "1") (pinfunction "A_1") (pintype "passive"))
      (node (ref "P0") (pin "1") (pinfunction "1_1") (pintype "passive"))
    )
    (net (code "139") (name "Net-(D1-K)") (class "Default")
      (node (ref "D1") (pin "2") (pinfunction "K_2") (pintype "passive"))
      (node (ref "F1") (pin "1") (pinfunction "1_1") (pintype "passive"))
    )
    (net (code "140") (name "Net-(D2-K)") (class "Default")
      (node (ref "D2") (pin "2") (pinfunction "K_2") (pintype "passive"))
      (node (ref "P21") (pin "1") (pinfunction "1_1") (pintype "passive"))
      (node (ref "Q2") (pin "3") (pinfunction "D_3") (pintype "passive"))
    )
    (net (code "141") (name "Net-(D4-K)") (class "Default")
      (node (ref "C21") (pin "1") (pinfunction "1_1") (pintype "passive"))
      (node (ref "D4") (pin "2") (pinfunction "K_2") (pintype "passive"))
      (node (ref "U16") (pin "2") (pinfunction "VIN_2") (pintype "passive"))
    )
    (net (code "142") (name "Net-(D5-K)") (class "Default")
      (node (ref "C5") (pin "1") (pinfunction "1_1") (pintype "passive"))
      (node (ref "D5") (pin "2") (pinfunction "K_2") (pintype "passive"))
      (node (ref "U4") (pin "2") (pinfunction "VIN_2") (pintype "passive"))
    )
    (net (code "143") (name "Net-(D7-K)") (class "Default")
      (node (ref "C15") (pin "1") (pinfunction "1_1") (pintype "passive"))
      (node (ref "D7") (pin "2") (pinfunction "K_2") (pintype "passive"))
      (node (ref "L3") (pin "1") (pinfunction "1_1") (pintype "passive"))
      (node (ref "U1") (pin "3") (pinfunction "SW_3") (pintype "passive"))
    )
    (net (code "144") (name "Net-(D8-K)") (class "Default")
      (node (ref "C49") (pin "1") (pinfunction "1_1") (pintype "passive"))
      (node (ref "D8") (pin "2") (pinfunction "K_2") (pintype "passive"))
      (node (ref "L4") (pin "1") (pinfunction "1_1") (pintype "passive"))
      (node (ref "U2") (pin "3") (pinfunction "SW_3") (pintype "passive"))
    )
    (net (code "145") (name "Net-(LD0-A)") (class "Default")
      (node (ref "LD0") (pin "1") (pinfunction "A_1") (pintype "passive"))
      (node (ref "R3") (pin "2") (pinfunction "2_2") (pintype "passive"))
    )
    (net (code "146") (name "Net-(P13-Pad1)") (class "Default")
      (node (ref "P13") (pin "1") (pinfunction "1_1") (pintype "passive"))
      (node (ref "R25") (pin "2") (pinfunction "2_2") (pintype "passive"))
    )
    (net (code "147") (name "Net-(P19-Pad1)") (class "Default")
      (node (ref "P19") (pin "1") (pinfunction "1_1") (pintype "passive"))
      (node (ref "U9") (pin "5") (pinfunction "FO_5") (pintype "passive"))
      (node (ref "U9") (pin "6") (pinfunction "FO_6") (pintype "passive"))
    )
    (net (code "148") (name "Net-(P19-Pad2)") (class "Default")
      (node (ref "P19") (pin "2") (pinfunction "2_2") (pintype "passive"))
      (node (ref "U9") (pin "7") (pinfunction "BO_7") (pintype "passive"))
      (node (ref "U9") (pin "8") (pinfunction "BO_8") (pintype "passive"))
    )
    (net (code "149") (name "Net-(P20-Pad1)") (class "Default")
      (node (ref "P20") (pin "1") (pinfunction "1_1") (pintype "passive"))
      (node (ref "R34") (pin "1") (pinfunction "1_1") (pintype "passive"))
      (node (ref "R35") (pin "1") (pinfunction "1_1") (pintype "passive"))
    )
    (net (code "150") (name "Net-(P22-Pad1)") (class "Default")
      (node (ref "P22") (pin "1") (pinfunction "1_1") (pintype "passive"))
      (node (ref "R24") (pin "2") (pinfunction "2_2") (pintype "passive"))
    )
    (net (code "151") (name "Net-(P23-Pad2)") (class "Default")
      (node (ref "P23") (pin "2") (pinfunction "2_2") (pintype "passive"))
      (node (ref "R43") (pin "1") (pinfunction "1_1") (pintype "passive"))
    )
    (net (code "152") (name "Net-(Q2-G)") (class "Default")
      (node (ref "Q2") (pin "1") (pinfunction "G_1") (pintype "passive"))
      (node (ref "R28") (pin "1") (pinfunction "1_1") (pintype "passive"))
      (node (ref "R29") (pin "2") (pinfunction "2_2") (pintype "passive"))
    )
    (net (code "153") (name "Net-(Q3-D)") (class "Default")
      (node (ref "Q3") (pin "3") (pinfunction "D_3") (pintype "passive"))
      (node (ref "R34") (pin "2") (pinfunction "2_2") (pintype "passive"))
      (node (ref "R35") (pin "2") (pinfunction "2_2") (pintype "passive"))
    )
    (net (code "154") (name "Net-(Q3-G)") (class "Default")
      (node (ref "Q3") (pin "1") (pinfunction "G_1") (pintype "passive"))
      (node (ref "R32") (pin "1") (pinfunction "1_1") (pintype "passive"))
      (node (ref "R33") (pin "2") (pinfunction "2_2") (pintype "passive"))
    )
    (net (code "155") (name "Net-(Q5-B)") (class "Default")
      (node (ref "C31") (pin "1") (pinfunction "1_1") (pintype "passive"))
      (node (ref "Q5") (pin "1") (pinfunction "B_1") (pintype "passive"))
      (node (ref "R26") (pin "2") (pinfunction "2_2") (pintype "passive"))
      (node (ref "R27") (pin "2") (pinfunction "2_2") (pintype "passive"))
    )
    (net (code "156") (name "Net-(Q5-C)") (class "Default")
      (node (ref "Q5") (pin "3") (pinfunction "C_3") (pintype "passive"))
      (node (ref "R29") (pin "1") (pinfunction "1_1") (pintype "passive"))
    )
    (net (code "157") (name "Net-(Q6-B)") (class "Default")
      (node (ref "Q6") (pin "1") (pinfunction "B_1") (pintype "passive"))
      (node (ref "R30") (pin "2") (pinfunction "2_2") (pintype "passive"))
      (node (ref "R31") (pin "2") (pinfunction "2_2") (pintype "passive"))
    )
    (net (code "158") (name "Net-(Q6-C)") (class "Default")
      (node (ref "Q6") (pin "3") (pinfunction "C_3") (pintype "passive"))
      (node (ref "R33") (pin "1") (pinfunction "1_1") (pintype "passive"))
    )
    (net (code "159") (name "Net-(Q7-B)") (class "Default")
      (node (ref "Q7") (pin "1") (pinfunction "B_1") (pintype "passive"))
      (node (ref "R20") (pin "2") (pinfunction "2_2") (pintype "passive"))
      (node (ref "R21") (pin "2") (pinfunction "2_2") (pintype "passive"))
    )
    (net (code "160") (name "Net-(Q7-C)") (class "Default")
      (node (ref "LS1") (pin "2") (pinfunction "2_2") (pintype "passive"))
      (node (ref "Q7") (pin "3") (pinfunction "C_3") (pintype "passive"))
    )
    (net (code "161") (name "Net-(R63-Pad1)") (class "Default")
      (node (ref "R63") (pin "1") (pinfunction "1_1") (pintype "passive"))
      (node (ref "R64") (pin "2") (pinfunction "2_2") (pintype "passive"))
      (node (ref "R65") (pin "2") (pinfunction "2_2") (pintype "passive"))
    )
    (net (code "162") (name "Net-(U1-BS)") (class "Default")
      (node (ref "C15") (pin "2") (pinfunction "2_2") (pintype "passive"))
      (node (ref "U1") (pin "1") (pinfunction "BS_1") (pintype "passive"))
    )
    (net (code "163") (name "Net-(U1-COMP)") (class "Default")
      (node (ref "C18") (pin "1") (pinfunction "1_1") (pintype "passive"))
      (node (ref "U1") (pin "6") (pinfunction "COMP_6") (pintype "passive"))
    )
    (net (code "164") (name "Net-(U1-EN)") (class "Default")
      (node (ref "R1") (pin "1") (pinfunction "1_1") (pintype "passive"))
      (node (ref "U1") (pin "7") (pinfunction "EN_7") (pintype "passive"))
    )
    (net (code "165") (name "Net-(U1-FB)") (class "Default")
      (node (ref "R4") (pin "2") (pinfunction "2_2") (pintype "passive"))
      (node (ref "R5") (pin "1") (pinfunction "1_1") (pintype "passive"))
      (node (ref "U1") (pin "5") (pinfunction "FB_5") (pintype "passive"))
    )
    (net (code "166") (name "Net-(U1-SS)") (class "Default")
      (node (ref "C17") (pin "1") (pinfunction "1_1") (pintype "passive"))
      (node (ref "U1") (pin "8") (pinfunction "SS_8") (pintype "passive"))
    )
    (net (code "167") (name "Net-(U2-BS)") (class "Default")
      (node (ref "C49") (pin "2") (pinfunction "2_2") (pintype "passive"))
      (node (ref "U2") (pin "1") (pinfunction "BS_1") (pintype "passive"))
    )
    (net (code "168") (name "Net-(U2-COMP)") (class "Default")
      (node (ref "C51") (pin "1") (pinfunction "1_1") (pintype "passive"))
      (node (ref "U2") (pin "6") (pinfunction "COMP_6") (pintype "passive"))
    )
    (net (code "169") (name "Net-(U2-EN)") (class "Default")
      (node (ref "R6") (pin "1") (pinfunction "1_1") (pintype "passive"))
      (node (ref "U2") (pin "7") (pinfunction "EN_7") (pintype "passive"))
    )
    (net (code "170") (name "Net-(U2-FB)") (class "Default")
      (node (ref "R7") (pin "2") (pinfunction "2_2") (pintype "passive"))
      (node (ref "R8") (pin "1") (pinfunction "1_1") (pintype "passive"))
      (node (ref "U2") (pin "5") (pinfunction "FB_5") (pintype "passive"))
    )
    (net (code "171") (name "Net-(U2-SS)") (class "Default")
      (node (ref "C50") (pin "1") (pinfunction "1_1") (pintype "passive"))
      (node (ref "U2") (pin "8") (pinfunction "SS_8") (pintype "passive"))
    )
    (net (code "172") (name "Net-(U5-{slash}SRCLR)") (class "Default")
      (node (ref "R68") (pin "2") (pinfunction "2_2") (pintype "passive"))
      (node (ref "U5") (pin "10") (pinfunction "/SRCLR_10") (pintype "passive"))
    )
    (net (code "173") (name "Net-(U6-PA5)") (class "Default")
      (node (ref "R66") (pin "2") (pinfunction "2_2") (pintype "passive"))
      (node (ref "R76") (pin "1") (pinfunction "1_1") (pintype "passive"))
      (node (ref "U6") (pin "15") (pinfunction "PA5_15") (pintype "bidirectional"))
    )
    (net (code "174") (name "Net-(U6-PA6)") (class "Default")
      (node (ref "R70") (pin "2") (pinfunction "2_2") (pintype "passive"))
      (node (ref "R75") (pin "2") (pinfunction "2_2") (pintype "passive"))
      (node (ref "U6") (pin "16") (pinfunction "PA6_16") (pintype "bidirectional"))
    )
    (net (code "175") (name "Net-(U6-PA7)") (class "Default")
      (node (ref "R79") (pin "2") (pinfunction "2_2") (pintype "passive"))
      (node (ref "U6") (pin "17") (pinfunction "PA7_17") (pintype "bidirectional"))
    )
    (net (code "176") (name "Net-(U6-PA12)") (class "Default")
      (node (ref "R61") (pin "2") (pinfunction "2_2") (pintype "passive"))
      (node (ref "U6") (pin "33") (pinfunction "PA12_33") (pintype "bidirectional"))
    )
    (net (code "177") (name "Net-(U6-PA15{slash}JTDI)") (class "Default")
      (node (ref "R62") (pin "2") (pinfunction "2_2") (pintype "passive"))
      (node (ref "U6") (pin "38") (pinfunction "PA15/JTDI_38") (pintype "bidirectional"))
    )
    (net (code "178") (name "Net-(U6-PB8)") (class "Default")
      (node (ref "R53") (pin "2") (pinfunction "2_2") (pintype "passive"))
      (node (ref "U6") (pin "45") (pinfunction "PB8_45") (pintype "bidirectional"))
    )
    (net (code "179") (name "Net-(U6-PB12)") (class "Default")
      (node (ref "R59") (pin "2") (pinfunction "2_2") (pintype "passive"))
      (node (ref "U6") (pin "25") (pinfunction "PB12_25") (pintype "bidirectional"))
    )
    (net (code "180") (name "Net-(U6-PB13)") (class "Default")
      (node (ref "R60") (pin "2") (pinfunction "2_2") (pintype "passive"))
      (node (ref "U6") (pin "26") (pinfunction "PB13_26") (pintype "bidirectional"))
    )
    (net (code "181") (name "Net-(U6-VDDA)") (class "Default")
      (node (ref "C27") (pin "1") (pinfunction "1_1") (pintype "passive"))
      (node (ref "R15") (pin "1") (pinfunction "1_1") (pintype "passive"))
      (node (ref "U6") (pin "9") (pinfunction "VDDA_9") (pintype "power_in"))
    )
    (net (code "182") (name "Net-(U9-BI)") (class "Default")
      (node (ref "R22") (pin "2") (pinfunction "2_2") (pintype "passive"))
      (node (ref "U9") (pin "1") (pinfunction "BI_1") (pintype "passive"))
    )
    (net (code "183") (name "Net-(U9-FI)") (class "Default")
      (node (ref "R23") (pin "1") (pinfunction "1_1") (pintype "passive"))
      (node (ref "U9") (pin "2") (pinfunction "FI_2") (pintype "passive"))
    )
    (net (code "184") (name "Net-(U13-In1-)") (class "Default")
      (node (ref "R39") (pin "2") (pinfunction "2_2") (pintype "passive"))
      (node (ref "U13") (pin "1") (pinfunction "Out1_1") (pintype "passive"))
      (node (ref "U13") (pin "2") (pinfunction "In1-_2") (pintype "passive"))
    )
    (net (code "185") (name "Net-(U13-In2-)") (class "Default")
      (node (ref "R64") (pin "1") (pinfunction "1_1") (pintype "passive"))
      (node (ref "U13") (pin "6") (pinfunction "In2-_6") (pintype "passive"))
      (node (ref "U13") (pin "7") (pinfunction "Out2_7") (pintype "passive"))
    )
    (net (code "186") (name "Net-(U14-{slash}SRCLR)") (class "Default")
      (node (ref "R69") (pin "2") (pinfunction "2_2") (pintype "passive"))
      (node (ref "U14") (pin "10") (pinfunction "/SRCLR_10") (pintype "passive"))
    )
    (net (code "187") (name "Net-(U15-{slash}SRCLR)") (class "Default")
      (node (ref "R67") (pin "2") (pinfunction "2_2") (pintype "passive"))
      (node (ref "U15") (pin "10") (pinfunction "/SRCLR_10") (pintype "passive"))
    )
    (net (code "188") (name "unconnected-(U6-PB9-Pad46)") (class "Default")
      (node (ref "U6") (pin "46") (pinfunction "PB9_46") (pintype "bidirectional"))
    )
    (net (code "189") (name "unconnected-(U7-X6-Pad2)") (class "Default")
      (node (ref "U7") (pin "2") (pinfunction "X6_2") (pintype "passive"))
    )
    (net (code "190") (name "unconnected-(U7-X7-Pad4)") (class "Default")
      (node (ref "U7") (pin "4") (pinfunction "X7_4") (pintype "passive"))
    )
    (net (code "191") (name "unconnected-(U8-X6-Pad2)") (class "Default")
      (node (ref "U8") (pin "2") (pinfunction "X6_2") (pintype "passive"))
    )
    (net (code "192") (name "unconnected-(U8-X7-Pad4)") (class "Default")
      (node (ref "U8") (pin "4") (pinfunction "X7_4") (pintype "passive"))
    )
    (net (code "193") (name "unconnected-(U10-X6-Pad2)") (class "Default")
      (node (ref "U10") (pin "2") (pinfunction "X6_2") (pintype "passive"))
    )
    (net (code "194") (name "unconnected-(U10-X7-Pad4)") (class "Default")
      (node (ref "U10") (pin "4") (pinfunction "X7_4") (pintype "passive"))
    )
    (net (code "195") (name "unconnected-(U11-X6-Pad2)") (class "Default")
      (node (ref "U11") (pin "2") (pinfunction "X6_2") (pintype "passive"))
    )
    (net (code "196") (name "unconnected-(U11-X7-Pad4)") (class "Default")
      (node (ref "U11") (pin "4") (pinfunction "X7_4") (pintype "passive"))
    )
    (net (code "197") (name "unconnected-(U12-X6-Pad2)") (class "Default")
      (node (ref "U12") (pin "2") (pinfunction "X6_2") (pintype "passive"))
    )
    (net (code "198") (name "unconnected-(U12-X7-Pad4)") (class "Default")
      (node (ref "U12") (pin "4") (pinfunction "X7_4") (pintype "passive"))
    )
    (net (code "199") (name "unconnected-(U15-QH'-Pad9)") (class "Default")
      (node (ref "U15") (pin "9") (pinfunction "QH'_9") (pintype "passive"))
    )
    (net (code "200") (name "unconnected-(U17-X6-Pad2)") (class "Default")
      (node (ref "U17") (pin "2") (pinfunction "X6_2") (pintype "passive"))
    )
    (net (code "201") (name "unconnected-(U17-X7-Pad4)") (class "Default")
      (node (ref "U17") (pin "4") (pinfunction "X7_4") (pintype "passive"))
    )
    (net (code "202") (name "unconnected-(U20-X6-Pad2)") (class "Default")
      (node (ref "U20") (pin "2") (pinfunction "X6_2") (pintype "passive"))
    )
    (net (code "203") (name "unconnected-(U20-X7-Pad4)") (class "Default")
      (node (ref "U20") (pin "4") (pinfunction "X7_4") (pintype "passive"))
    )
    (net (code "204") (name "unconnected-(U21-X6-Pad2)") (class "Default")
      (node (ref "U21") (pin "2") (pinfunction "X6_2") (pintype "passive"))
    )
    (net (code "205") (name "unconnected-(U21-X7-Pad4)") (class "Default")
      (node (ref "U21") (pin "4") (pinfunction "X7_4") (pintype "passive"))
    )
    (net (code "206") (name "unconnected-(U22-X2-Pad15)") (class "Default")
      (node (ref "U22") (pin "15") (pinfunction "X2_15") (pintype "passive+no_connect"))
    )
    (net (code "207") (name "unconnected-(U22-X3-Pad11)") (class "Default")
      (node (ref "U22") (pin "11") (pinfunction "X3_11") (pintype "passive+no_connect"))
    )
    (net (code "208") (name "unconnected-(U22-Y2-Pad2)") (class "Default")
      (node (ref "U22") (pin "2") (pinfunction "Y2_2") (pintype "passive+no_connect"))
    )
    (net (code "209") (name "unconnected-(U22-Y3-Pad4)") (class "Default")
      (node (ref "U22") (pin "4") (pinfunction "Y3_4") (pintype "passive+no_connect"))
    )
    (net (code "210") (name "unconnected-(Y1-GROUND-Pad2)") (class "Default")
      (node (ref "Y1") (pin "2") (pinfunction "GROUND_2") (pintype "passive"))
    )
    (net (code "211") (name "unconnected-(Y1-GROUND-Pad4)") (class "Default")
      (node (ref "Y1") (pin "4") (pinfunction "GROUND_4") (pintype "passive"))
    )
  )
)
